# axiom_beta_sensor_cmv12000_tht_v0_16_r1_.net
KiCad netlist of a schematic drawn in EAGLE
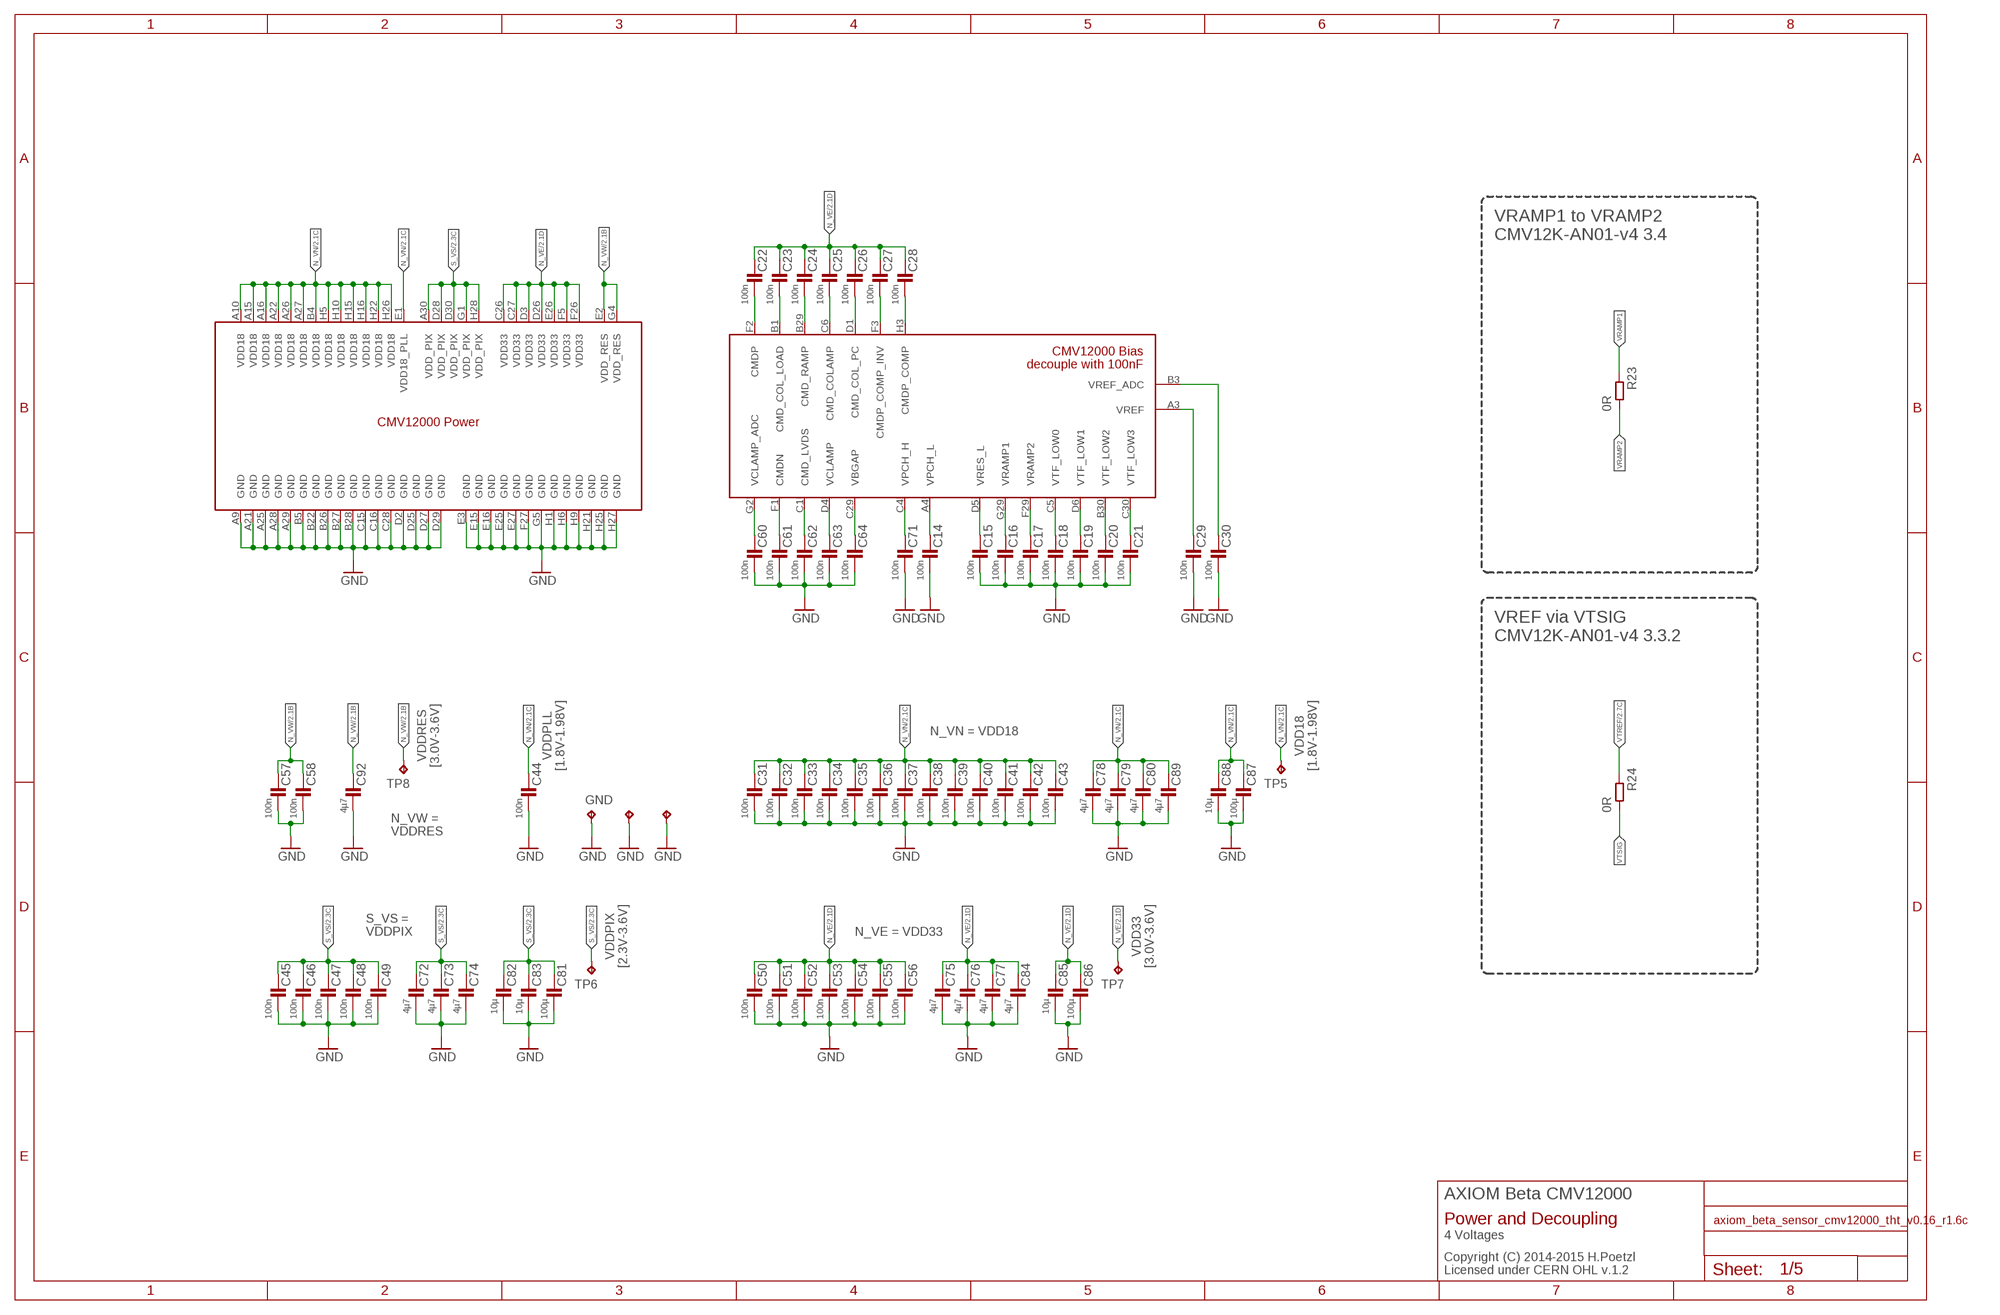
[diagram p0: schematic, sheet 1]
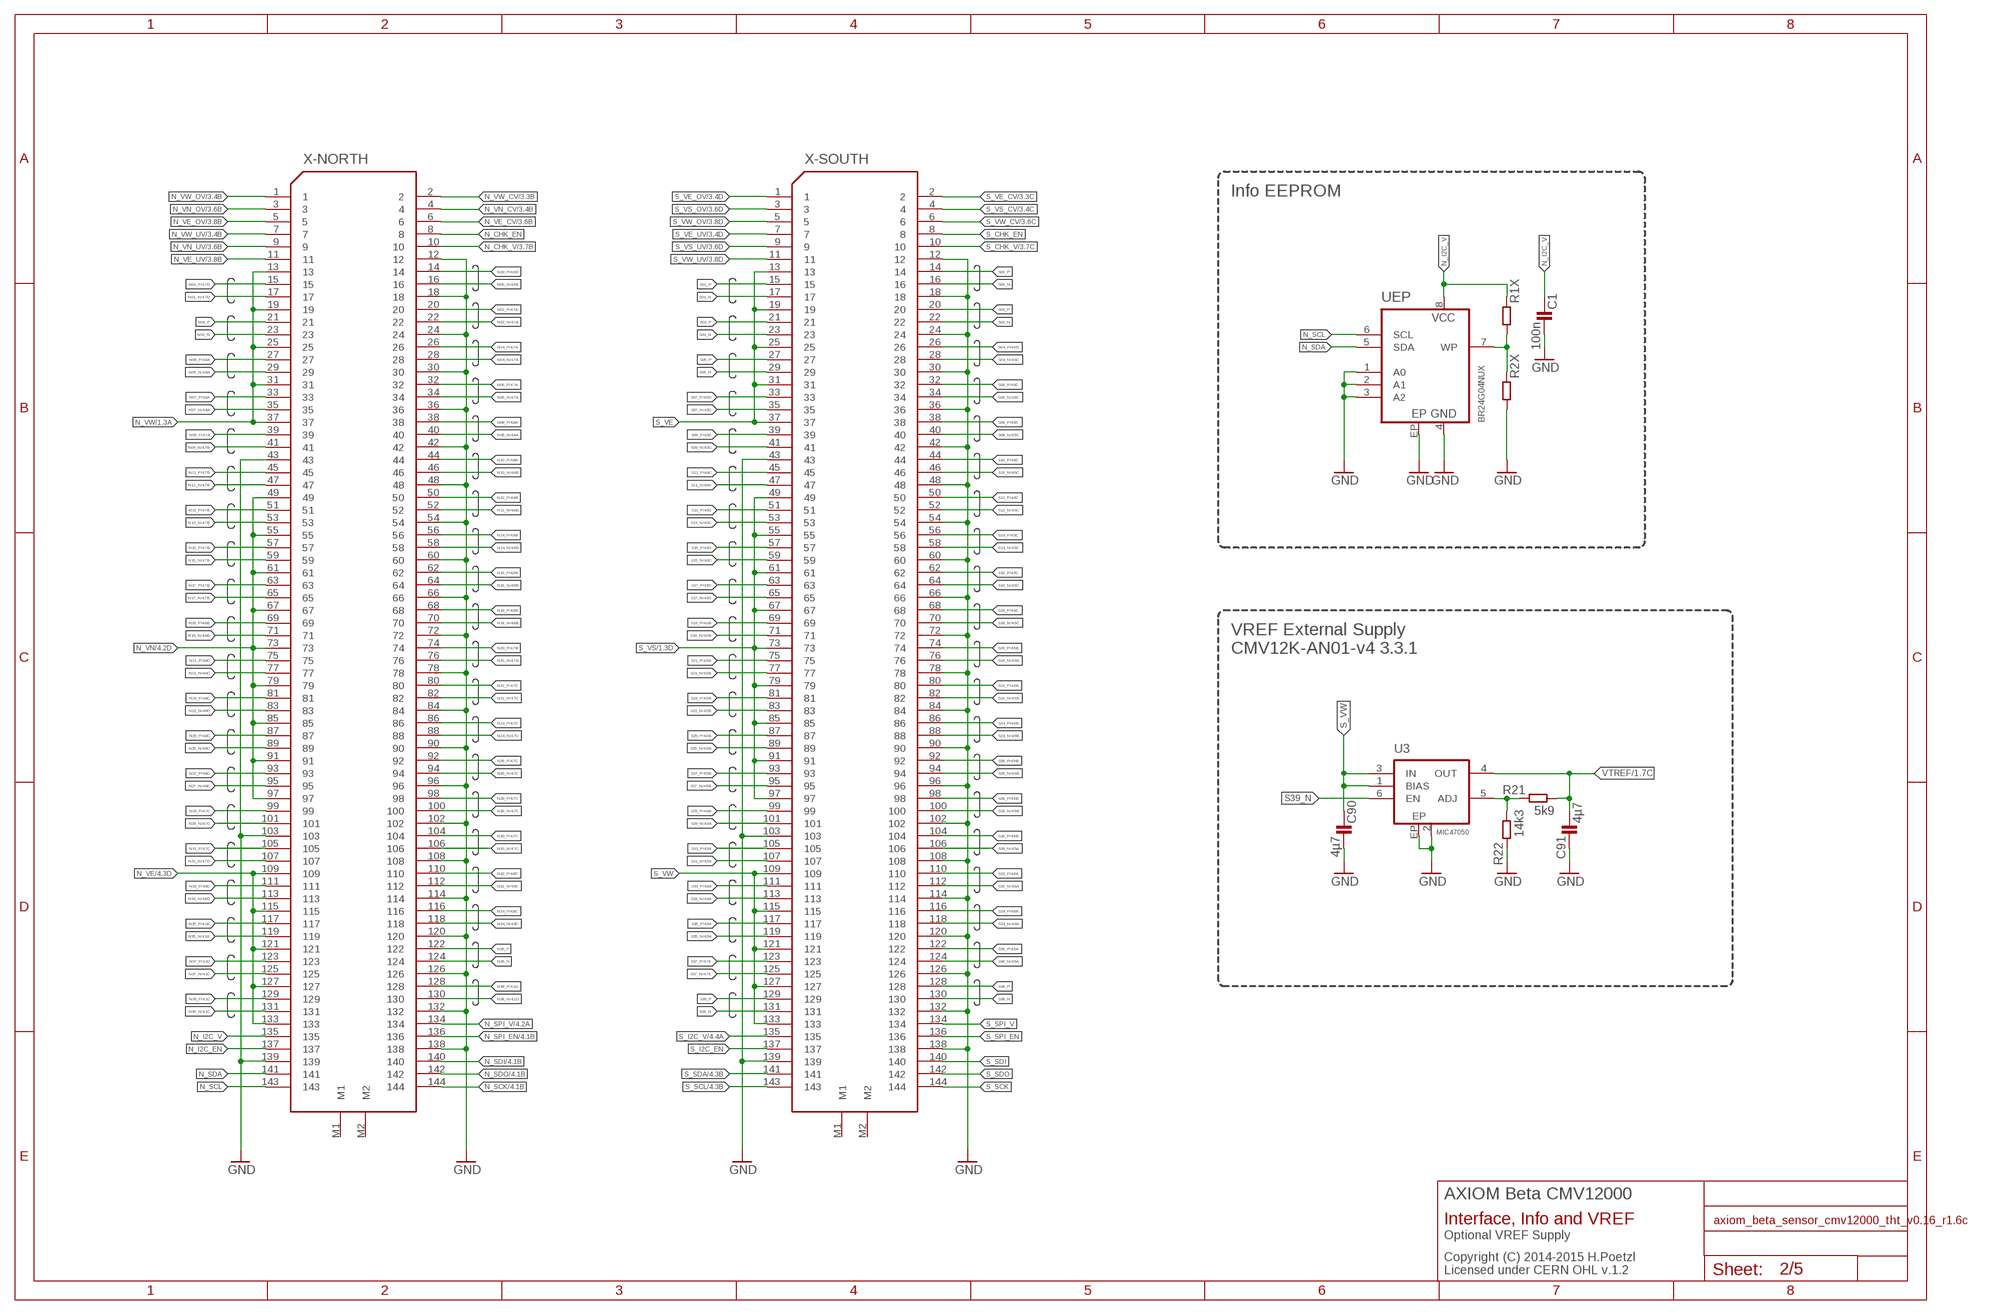
[diagram p1: schematic, sheet 2]
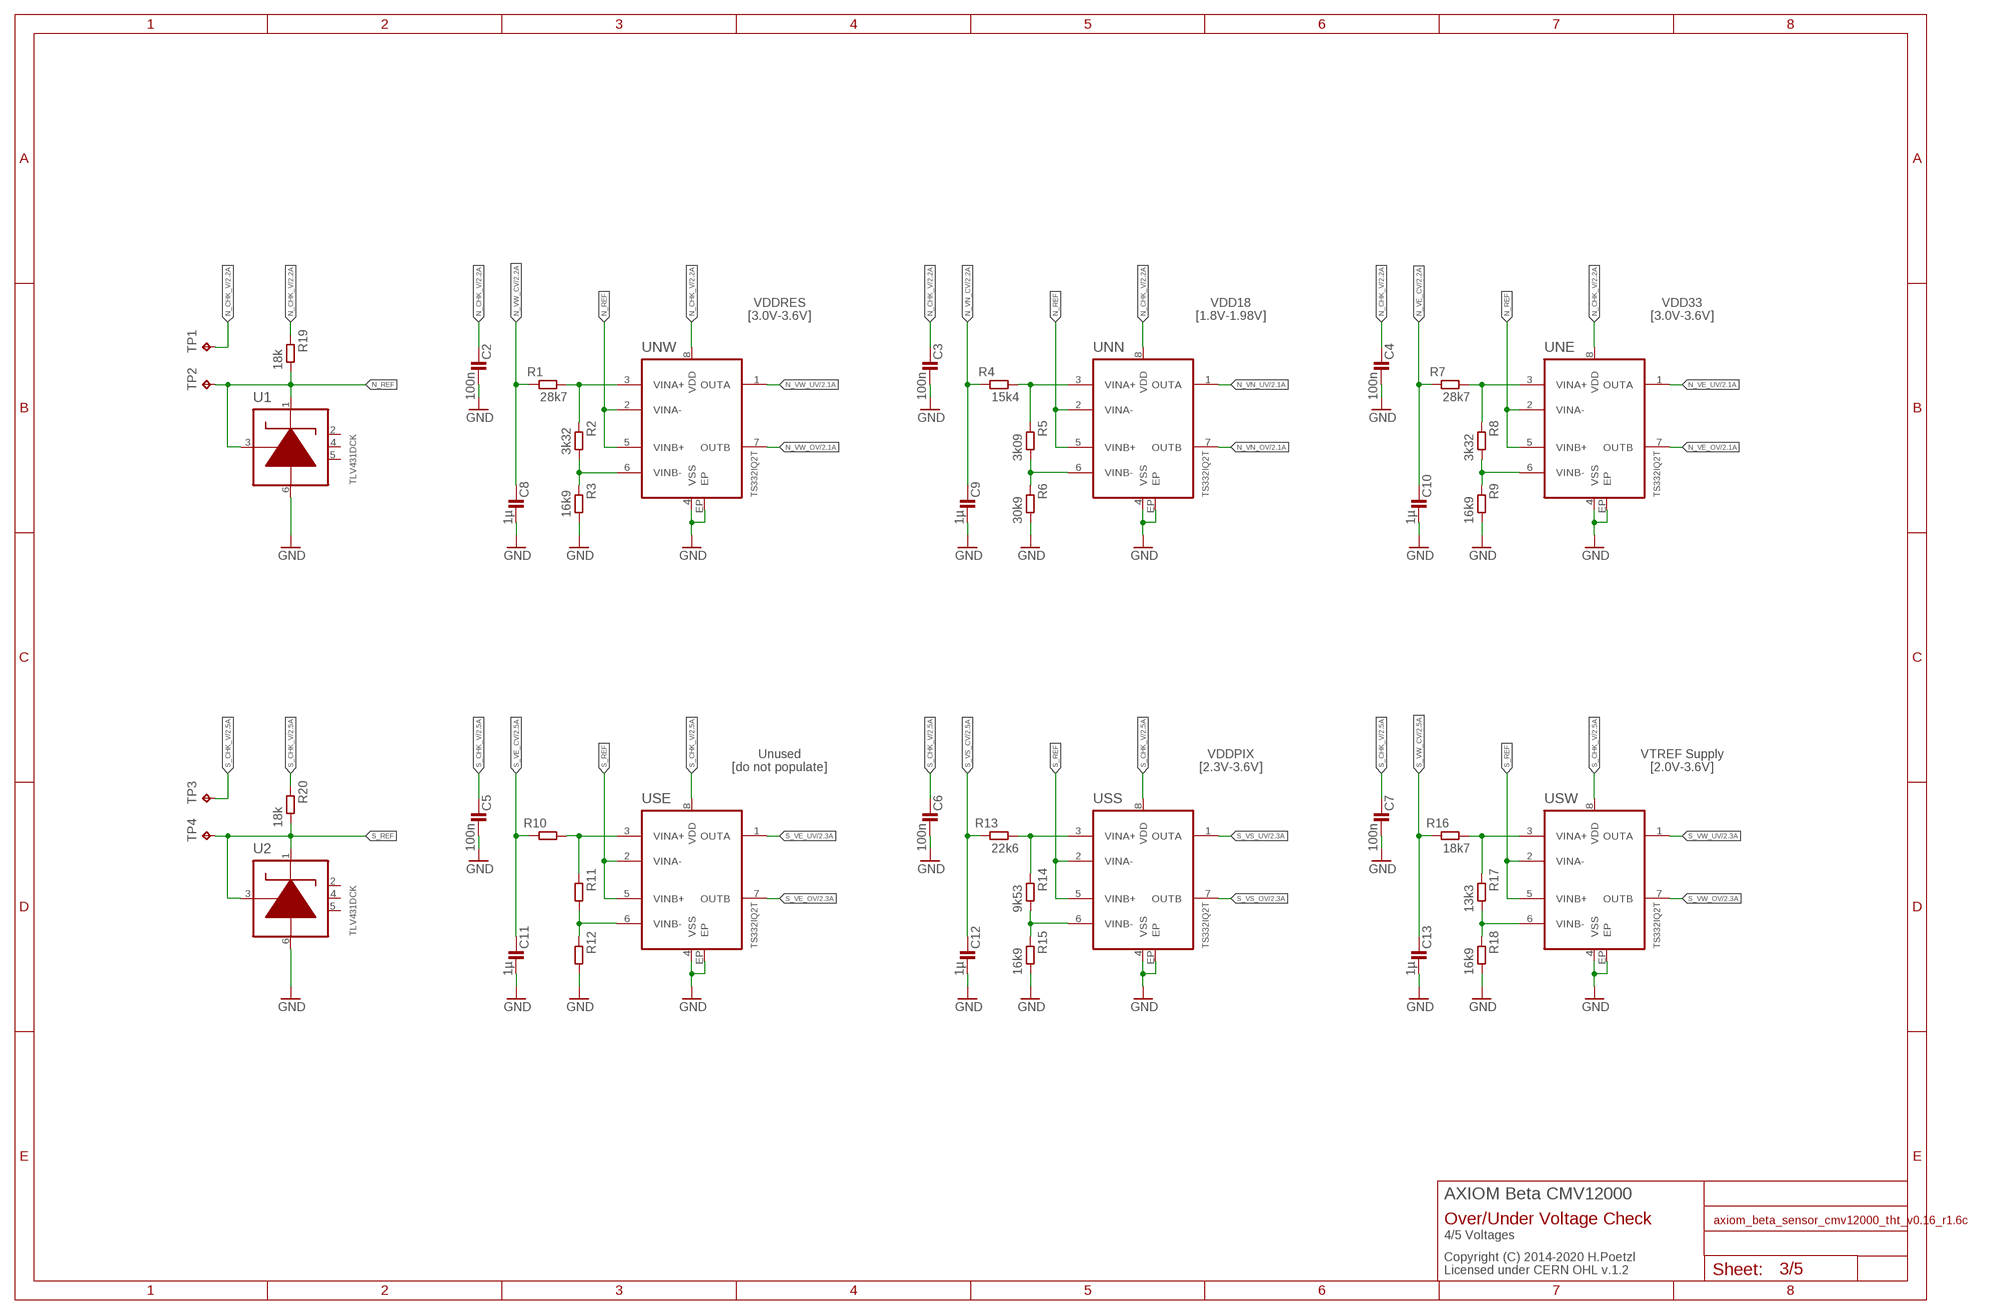
[diagram p2: schematic, sheet 3]
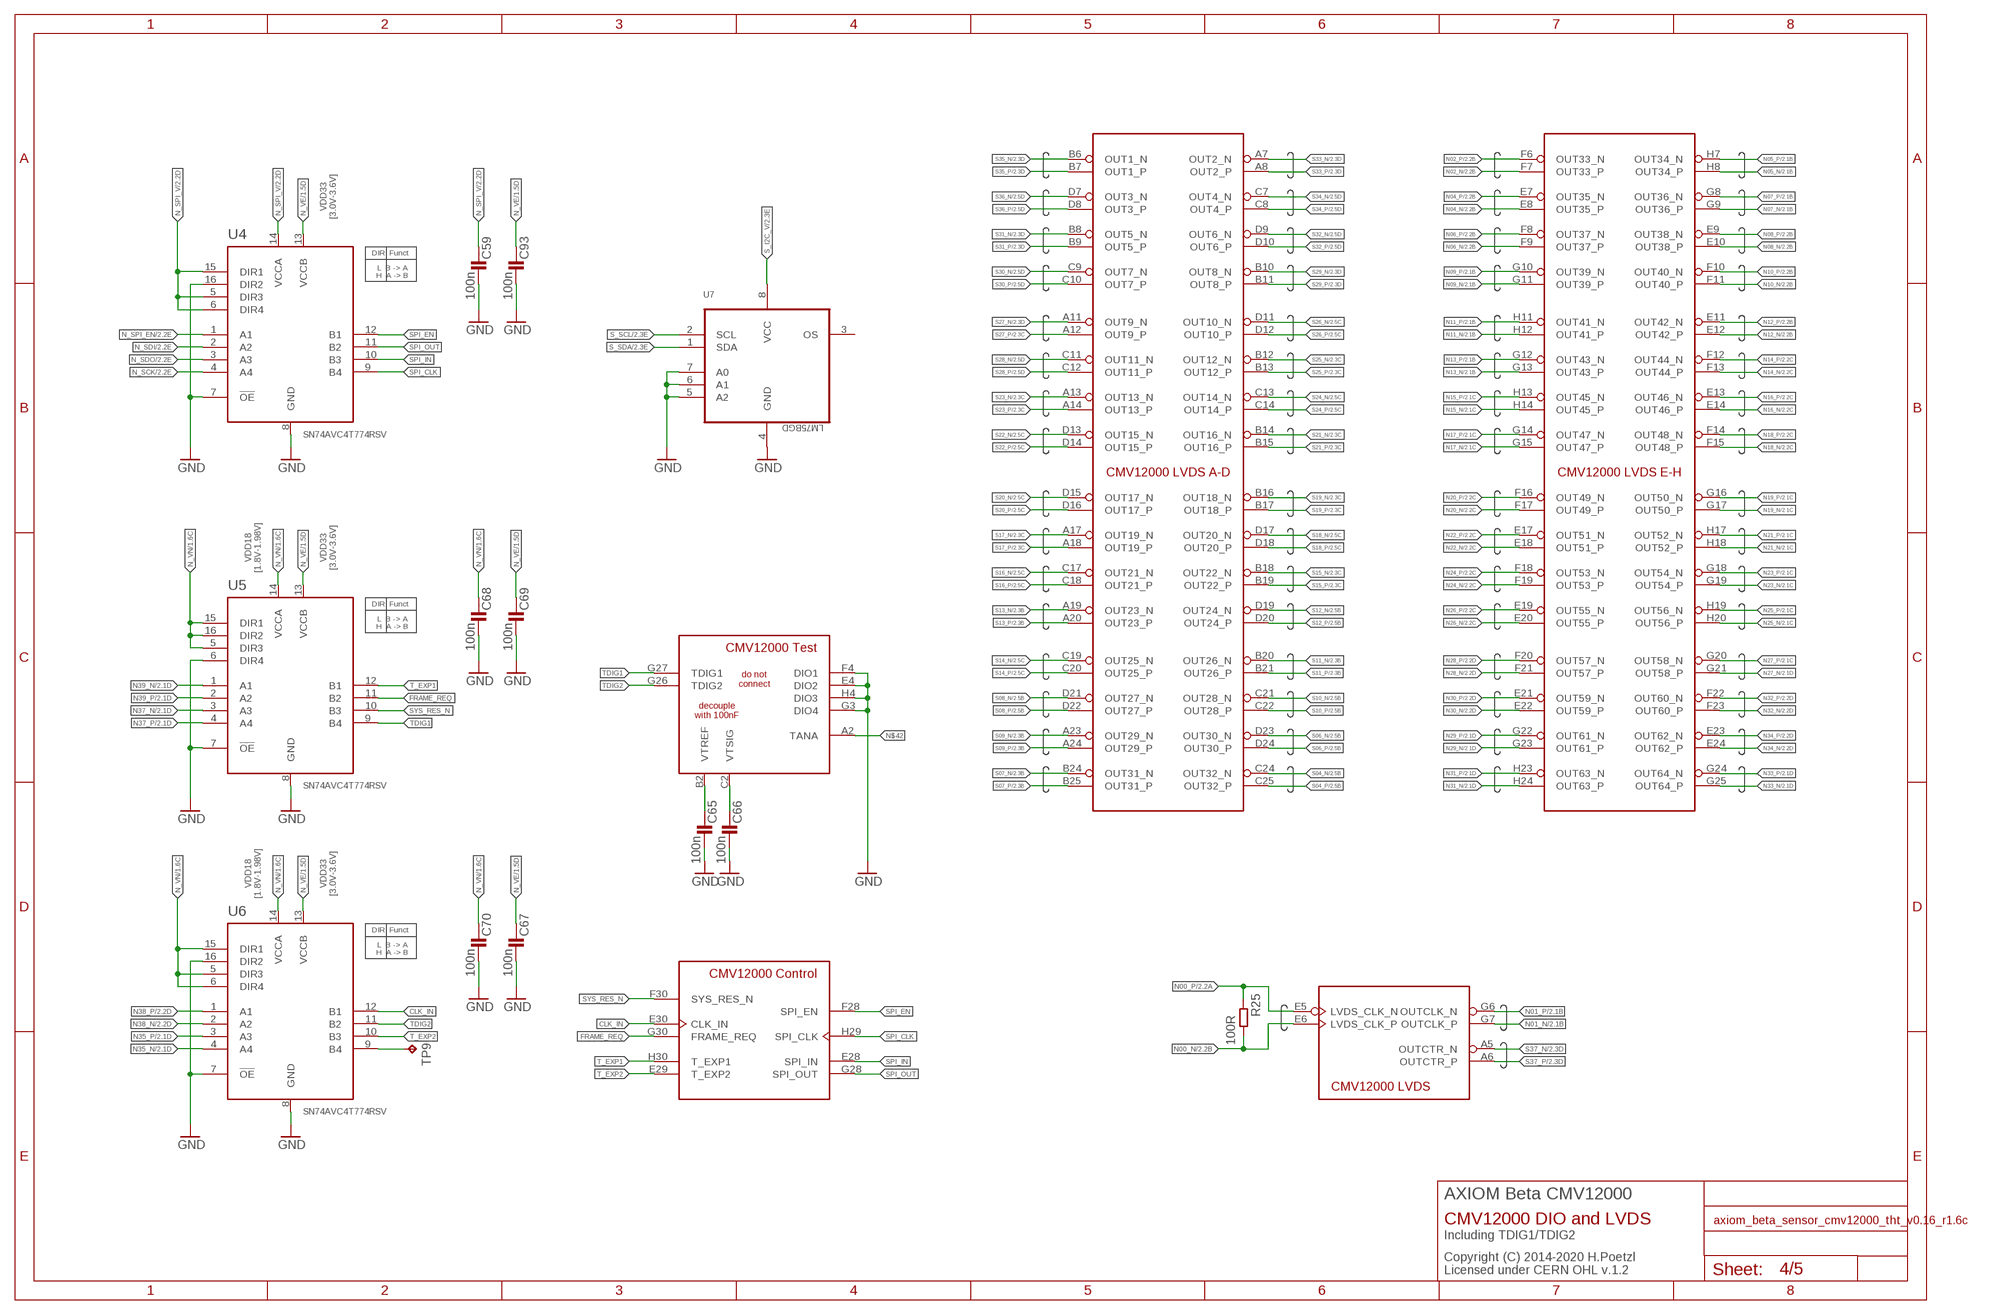
[diagram p3: schematic, sheet 4]
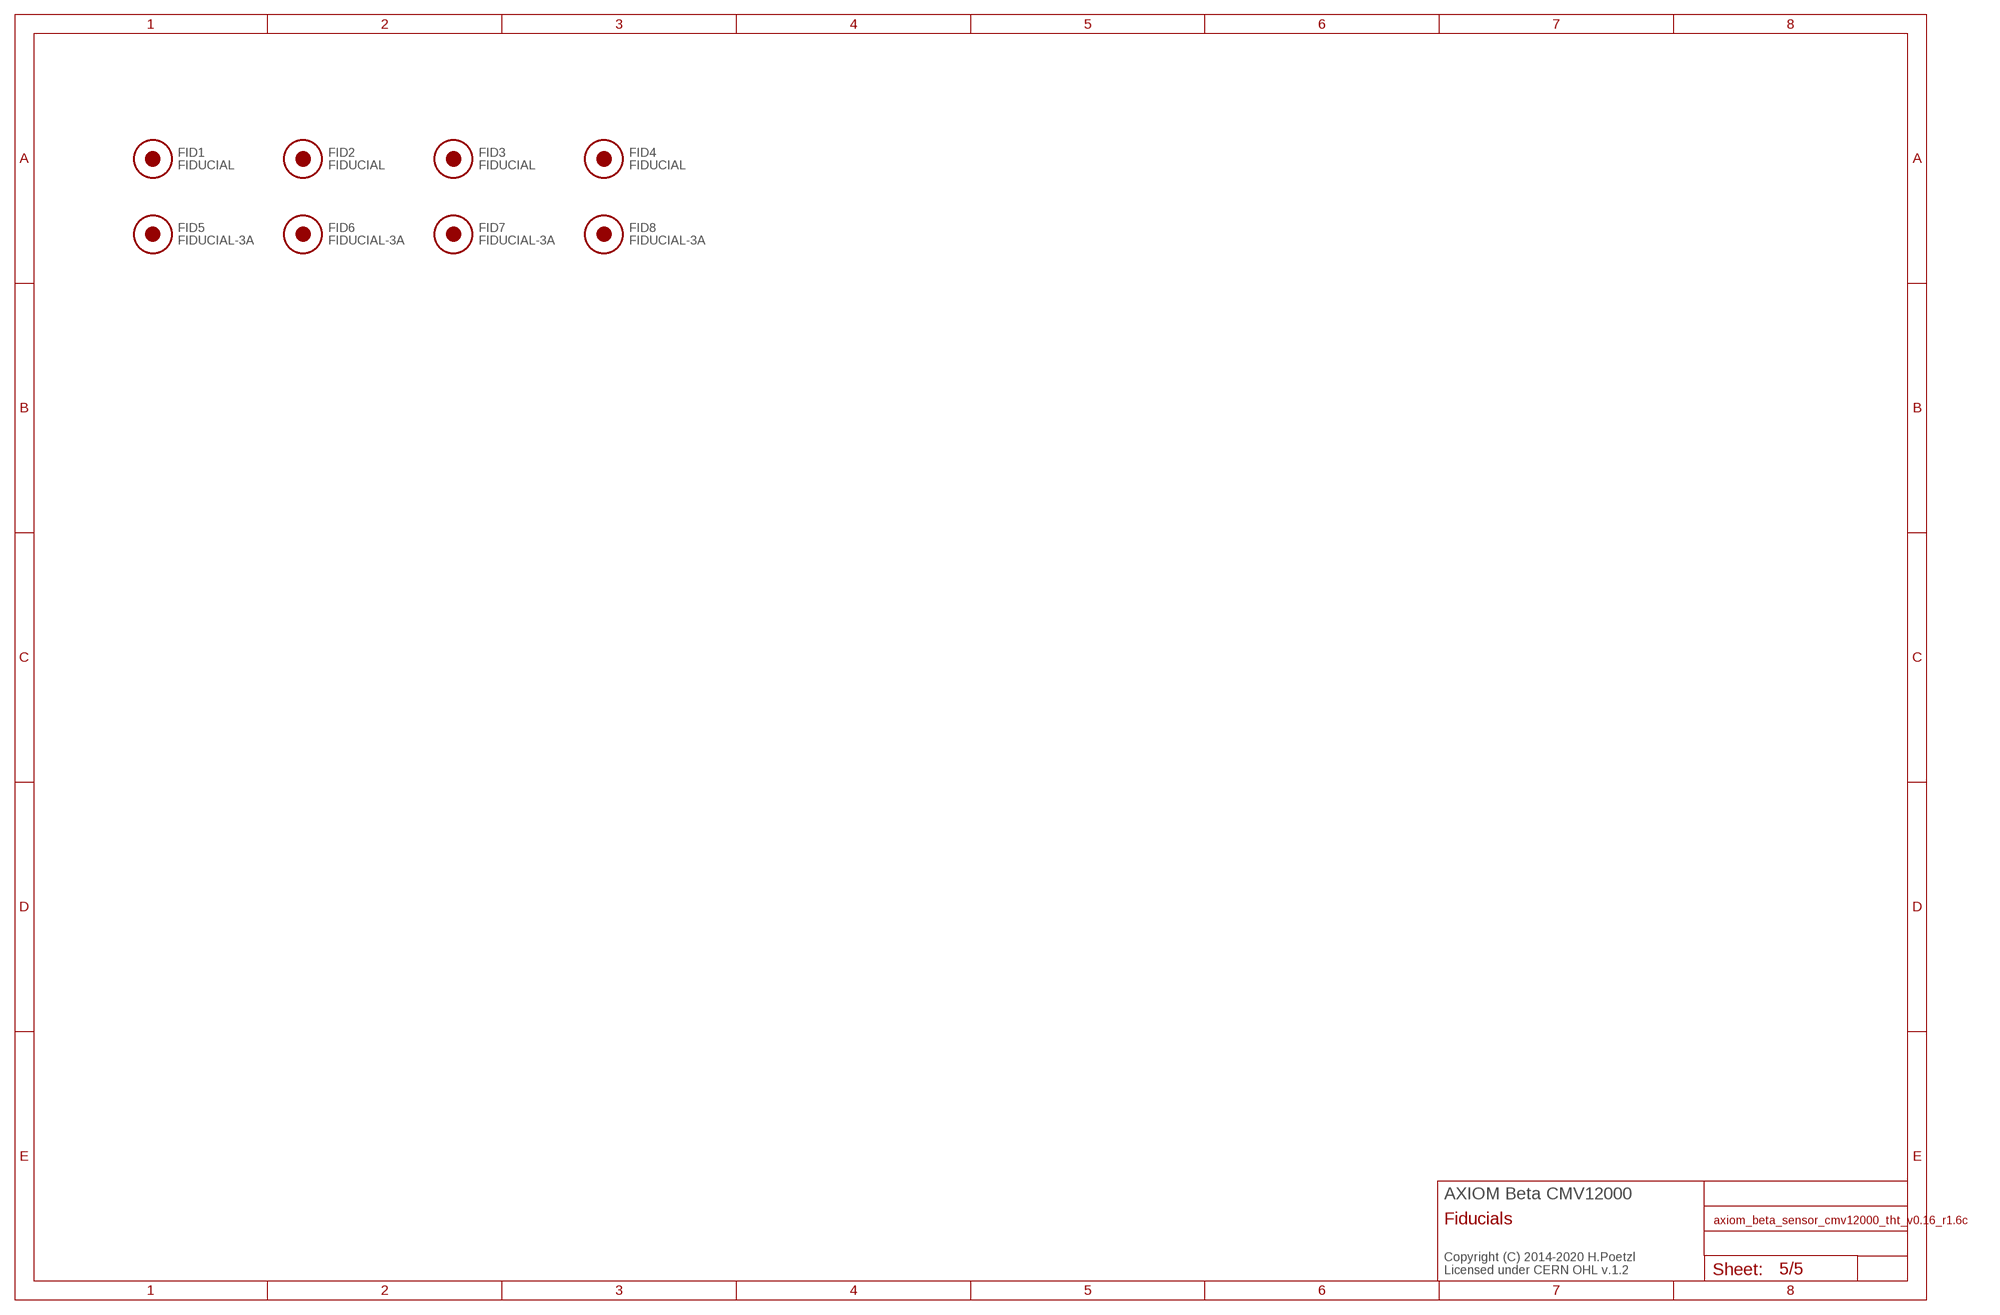
[diagram p4: schematic, sheet 5]

(export (version "E")
  (design (tool "Eeschema 10.0.6"))
  (components
    (comp (ref "C2")
      (value "100n")
      (footprint "eagle-import:0402-C")
      (libsource (lib "eagle-import") (part "C0402-C"))
    )
    (comp (ref "C3")
      (value "100n")
      (footprint "eagle-import:0402-C")
      (libsource (lib "eagle-import") (part "C0402-C"))
    )
    (comp (ref "C4")
      (value "100n")
      (footprint "eagle-import:0402-C")
      (libsource (lib "eagle-import") (part "C0402-C"))
    )
    (comp (ref "C5")
      (value "100n")
      (footprint "eagle-import:0402-C")
      (libsource (lib "eagle-import") (part "C0402-C"))
    )
    (comp (ref "C6")
      (value "100n")
      (footprint "eagle-import:0402-C")
      (libsource (lib "eagle-import") (part "C0402-C"))
    )
    (comp (ref "C7")
      (value "100n")
      (footprint "eagle-import:0402-C")
      (libsource (lib "eagle-import") (part "C0402-C"))
    )
    (comp (ref "C8")
      (value "1µ")
      (footprint "eagle-import:0402-C")
      (libsource (lib "eagle-import") (part "C0402-C"))
    )
    (comp (ref "C9")
      (value "1µ")
      (footprint "eagle-import:0402-C")
      (libsource (lib "eagle-import") (part "C0402-C"))
    )
    (comp (ref "C10")
      (value "1µ")
      (footprint "eagle-import:0402-C")
      (libsource (lib "eagle-import") (part "C0402-C"))
    )
    (comp (ref "C11")
      (value "1µ")
      (footprint "eagle-import:0402-C")
      (libsource (lib "eagle-import") (part "C0402-C"))
    )
    (comp (ref "C12")
      (value "1µ")
      (footprint "eagle-import:0402-C")
      (libsource (lib "eagle-import") (part "C0402-C"))
    )
    (comp (ref "C13")
      (value "1µ")
      (footprint "eagle-import:0402-C")
      (libsource (lib "eagle-import") (part "C0402-C"))
    )
    (comp (ref "R1")
      (value "28k7")
      (footprint "eagle-import:0402-C")
      (libsource (lib "eagle-import") (part "R0402-C"))
    )
    (comp (ref "R2")
      (value "3k32")
      (footprint "eagle-import:0402-C")
      (libsource (lib "eagle-import") (part "R0402-C"))
    )
    (comp (ref "R3")
      (value "16k9")
      (footprint "eagle-import:0402-C")
      (libsource (lib "eagle-import") (part "R0402-C"))
    )
    (comp (ref "R4")
      (value "15k4")
      (footprint "eagle-import:0402-C")
      (libsource (lib "eagle-import") (part "R0402-C"))
    )
    (comp (ref "R5")
      (value "3k09")
      (footprint "eagle-import:0402-C")
      (libsource (lib "eagle-import") (part "R0402-C"))
    )
    (comp (ref "R6")
      (value "30k9")
      (footprint "eagle-import:0402-C")
      (libsource (lib "eagle-import") (part "R0402-C"))
    )
    (comp (ref "R7")
      (value "28k7")
      (footprint "eagle-import:0402-C")
      (libsource (lib "eagle-import") (part "R0402-C"))
    )
    (comp (ref "R8")
      (value "3k32")
      (footprint "eagle-import:0402-C")
      (libsource (lib "eagle-import") (part "R0402-C"))
    )
    (comp (ref "R9")
      (value "16k9")
      (footprint "eagle-import:0402-C")
      (libsource (lib "eagle-import") (part "R0402-C"))
    )
    (comp (ref "R10")
      (value "R0402-C")
      (footprint "eagle-import:0402-C")
      (libsource (lib "eagle-import") (part "R0402-C"))
    )
    (comp (ref "R11")
      (value "R0402-C")
      (footprint "eagle-import:0402-C")
      (libsource (lib "eagle-import") (part "R0402-C"))
    )
    (comp (ref "R12")
      (value "R0402-C")
      (footprint "eagle-import:0402-C")
      (libsource (lib "eagle-import") (part "R0402-C"))
    )
    (comp (ref "R13")
      (value "22k6")
      (footprint "eagle-import:0402-C")
      (libsource (lib "eagle-import") (part "R0402-C"))
    )
    (comp (ref "R14")
      (value "9k53")
      (footprint "eagle-import:0402-C")
      (libsource (lib "eagle-import") (part "R0402-C"))
    )
    (comp (ref "R15")
      (value "16k9")
      (footprint "eagle-import:0402-C")
      (libsource (lib "eagle-import") (part "R0402-C"))
    )
    (comp (ref "R16")
      (value "18k7")
      (footprint "eagle-import:0402-C")
      (libsource (lib "eagle-import") (part "R0402-C"))
    )
    (comp (ref "R17")
      (value "13k3")
      (footprint "eagle-import:0402-C")
      (libsource (lib "eagle-import") (part "R0402-C"))
    )
    (comp (ref "R18")
      (value "16k9")
      (footprint "eagle-import:0402-C")
      (libsource (lib "eagle-import") (part "R0402-C"))
    )
    (comp (ref "R19")
      (value "18k")
      (footprint "eagle-import:0402-C")
      (libsource (lib "eagle-import") (part "R0402-C"))
    )
    (comp (ref "R20")
      (value "18k")
      (footprint "eagle-import:0402-C")
      (libsource (lib "eagle-import") (part "R0402-C"))
    )
    (comp (ref "TP1")
      (value "TPTP10R")
      (footprint "eagle-import:TP10R")
      (libsource (lib "eagle-import") (part "TPTP10R"))
    )
    (comp (ref "TP2")
      (value "TPTP10R")
      (footprint "eagle-import:TP10R")
      (libsource (lib "eagle-import") (part "TPTP10R"))
    )
    (comp (ref "TP3")
      (value "TPTP10R")
      (footprint "eagle-import:TP10R")
      (libsource (lib "eagle-import") (part "TPTP10R"))
    )
    (comp (ref "TP4")
      (value "TPTP10R")
      (footprint "eagle-import:TP10R")
      (libsource (lib "eagle-import") (part "TPTP10R"))
    )
    (comp (ref "U1")
      (value "TLV431DCK")
      (footprint "eagle-import:SOT65P210X110-6N")
      (libsource (lib "eagle-import") (part "TLV431DCK"))
    )
    (comp (ref "U2")
      (value "TLV431DCK")
      (footprint "eagle-import:SOT65P210X110-6N")
      (libsource (lib "eagle-import") (part "TLV431DCK"))
    )
    (comp (ref "UNE")
      (value "TS332IQ2T")
      (footprint "eagle-import:DFN200X200X100-9N")
      (libsource (lib "eagle-import") (part "TS332IQ2T"))
    )
    (comp (ref "UNN")
      (value "TS332IQ2T")
      (footprint "eagle-import:DFN200X200X100-9N")
      (libsource (lib "eagle-import") (part "TS332IQ2T"))
    )
    (comp (ref "UNW")
      (value "TS332IQ2T")
      (footprint "eagle-import:DFN200X200X100-9N")
      (libsource (lib "eagle-import") (part "TS332IQ2T"))
    )
    (comp (ref "USE")
      (value "TS332IQ2T")
      (footprint "eagle-import:DFN200X200X100-9N")
      (libsource (lib "eagle-import") (part "TS332IQ2T"))
    )
    (comp (ref "USS")
      (value "TS332IQ2T")
      (footprint "eagle-import:DFN200X200X100-9N")
      (libsource (lib "eagle-import") (part "TS332IQ2T"))
    )
    (comp (ref "USW")
      (value "TS332IQ2T")
      (footprint "eagle-import:DFN200X200X100-9N")
      (libsource (lib "eagle-import") (part "TS332IQ2T"))
    )
    (comp (ref "FID1")
      (value "FIDUCIAL")
      (footprint "eagle-import:FID_ARROW")
      (libsource (lib "eagle-import") (part "FIDUCIAL"))
    )
    (comp (ref "FID2")
      (value "FIDUCIAL")
      (footprint "eagle-import:FID_ARROW")
      (libsource (lib "eagle-import") (part "FIDUCIAL"))
    )
    (comp (ref "FID3")
      (value "FIDUCIAL")
      (footprint "eagle-import:FID_ARROW")
      (libsource (lib "eagle-import") (part "FIDUCIAL"))
    )
    (comp (ref "FID4")
      (value "FIDUCIAL")
      (footprint "eagle-import:FID_ARROW")
      (libsource (lib "eagle-import") (part "FIDUCIAL"))
    )
    (comp (ref "FID5")
      (value "FIDUCIAL-3A")
      (footprint "eagle-import:FID_3ARROW")
      (libsource (lib "eagle-import") (part "FIDUCIAL-3A"))
    )
    (comp (ref "FID6")
      (value "FIDUCIAL-3A")
      (footprint "eagle-import:FID_3ARROW")
      (libsource (lib "eagle-import") (part "FIDUCIAL-3A"))
    )
    (comp (ref "FID7")
      (value "FIDUCIAL-3A")
      (footprint "eagle-import:FID_3ARROW")
      (libsource (lib "eagle-import") (part "FIDUCIAL-3A"))
    )
    (comp (ref "FID8")
      (value "FIDUCIAL-3A")
      (footprint "eagle-import:FID_3ARROW")
      (libsource (lib "eagle-import") (part "FIDUCIAL-3A"))
    )
    (comp (ref "C59")
      (value "100n")
      (footprint "eagle-import:0402-C")
      (libsource (lib "eagle-import") (part "C0402-C"))
    )
    (comp (ref "C65")
      (value "100n")
      (footprint "eagle-import:0402-C")
      (libsource (lib "eagle-import") (part "C0402-C"))
    )
    (comp (ref "C66")
      (value "100n")
      (footprint "eagle-import:0402-C")
      (libsource (lib "eagle-import") (part "C0402-C"))
    )
    (comp (ref "C67")
      (value "100n")
      (footprint "eagle-import:0402-C")
      (libsource (lib "eagle-import") (part "C0402-C"))
    )
    (comp (ref "C68")
      (value "100n")
      (footprint "eagle-import:0402-C")
      (libsource (lib "eagle-import") (part "C0402-C"))
    )
    (comp (ref "C69")
      (value "100n")
      (footprint "eagle-import:0402-C")
      (libsource (lib "eagle-import") (part "C0402-C"))
    )
    (comp (ref "C70")
      (value "100n")
      (footprint "eagle-import:0402-C")
      (libsource (lib "eagle-import") (part "C0402-C"))
    )
    (comp (ref "C93")
      (value "100n")
      (footprint "eagle-import:0402-C")
      (libsource (lib "eagle-import") (part "C0402-C"))
    )
    (comp (ref "R25")
      (value "100R")
      (footprint "eagle-import:0402-C")
      (libsource (lib "eagle-import") (part "R0402-C"))
    )
    (comp (ref "SENSOR")
      (value "CMV12000ANDON")
      (footprint "eagle-import:10-30-07-237-400T4")
      (libsource (lib "eagle-import") (part "CMV12000ANDON"))
    )
    (comp (ref "TP9")
      (value "TPTP10R")
      (footprint "eagle-import:TP10R")
      (libsource (lib "eagle-import") (part "TPTP10R"))
    )
    (comp (ref "U4")
      (value "SN74AVC4T774RSV")
      (footprint "eagle-import:QFN40P185X265X55-16N")
      (libsource (lib "eagle-import") (part "SN74AVC4T774RSV"))
    )
    (comp (ref "U5")
      (value "SN74AVC4T774RSV")
      (footprint "eagle-import:QFN40P185X265X55-16N")
      (libsource (lib "eagle-import") (part "SN74AVC4T774RSV"))
    )
    (comp (ref "U6")
      (value "SN74AVC4T774RSV")
      (footprint "eagle-import:QFN40P185X265X55-16N")
      (libsource (lib "eagle-import") (part "SN74AVC4T774RSV"))
    )
    (comp (ref "U7")
      (value "LM75BGD")
      (footprint "eagle-import:SOT996-2_3")
      (libsource (lib "eagle-import") (part "LM75BGD"))
    )
    (comp (ref "C14")
      (value "100n")
      (footprint "eagle-import:0402-C")
      (libsource (lib "eagle-import") (part "C0402-C"))
    )
    (comp (ref "C15")
      (value "100n")
      (footprint "eagle-import:0402-C")
      (libsource (lib "eagle-import") (part "C0402-C"))
    )
    (comp (ref "C16")
      (value "100n")
      (footprint "eagle-import:0402-C")
      (libsource (lib "eagle-import") (part "C0402-C"))
    )
    (comp (ref "C17")
      (value "100n")
      (footprint "eagle-import:0402-C")
      (libsource (lib "eagle-import") (part "C0402-C"))
    )
    (comp (ref "C18")
      (value "100n")
      (footprint "eagle-import:0402-C")
      (libsource (lib "eagle-import") (part "C0402-C"))
    )
    (comp (ref "C19")
      (value "100n")
      (footprint "eagle-import:0402-C")
      (libsource (lib "eagle-import") (part "C0402-C"))
    )
    (comp (ref "C20")
      (value "100n")
      (footprint "eagle-import:0402-C")
      (libsource (lib "eagle-import") (part "C0402-C"))
    )
    (comp (ref "C21")
      (value "100n")
      (footprint "eagle-import:0402-C")
      (libsource (lib "eagle-import") (part "C0402-C"))
    )
    (comp (ref "C22")
      (value "100n")
      (footprint "eagle-import:0402-C")
      (libsource (lib "eagle-import") (part "C0402-C"))
    )
    (comp (ref "C23")
      (value "100n")
      (footprint "eagle-import:0402-C")
      (libsource (lib "eagle-import") (part "C0402-C"))
    )
    (comp (ref "C24")
      (value "100n")
      (footprint "eagle-import:0402-C")
      (libsource (lib "eagle-import") (part "C0402-C"))
    )
    (comp (ref "C25")
      (value "100n")
      (footprint "eagle-import:0402-C")
      (libsource (lib "eagle-import") (part "C0402-C"))
    )
    (comp (ref "C26")
      (value "100n")
      (footprint "eagle-import:0402-C")
      (libsource (lib "eagle-import") (part "C0402-C"))
    )
    (comp (ref "C27")
      (value "100n")
      (footprint "eagle-import:0402-C")
      (libsource (lib "eagle-import") (part "C0402-C"))
    )
    (comp (ref "C28")
      (value "100n")
      (footprint "eagle-import:0402-C")
      (libsource (lib "eagle-import") (part "C0402-C"))
    )
    (comp (ref "C29")
      (value "100n")
      (footprint "eagle-import:0402-C")
      (libsource (lib "eagle-import") (part "C0402-C"))
    )
    (comp (ref "C30")
      (value "100n")
      (footprint "eagle-import:0402-C")
      (libsource (lib "eagle-import") (part "C0402-C"))
    )
    (comp (ref "C31")
      (value "100n")
      (footprint "eagle-import:0402-C")
      (libsource (lib "eagle-import") (part "C0402-C"))
    )
    (comp (ref "C32")
      (value "100n")
      (footprint "eagle-import:0402-C")
      (libsource (lib "eagle-import") (part "C0402-C"))
    )
    (comp (ref "C33")
      (value "100n")
      (footprint "eagle-import:0402-C")
      (libsource (lib "eagle-import") (part "C0402-C"))
    )
    (comp (ref "C34")
      (value "100n")
      (footprint "eagle-import:0402-C")
      (libsource (lib "eagle-import") (part "C0402-C"))
    )
    (comp (ref "C35")
      (value "100n")
      (footprint "eagle-import:0402-C")
      (libsource (lib "eagle-import") (part "C0402-C"))
    )
    (comp (ref "C36")
      (value "100n")
      (footprint "eagle-import:0402-C")
      (libsource (lib "eagle-import") (part "C0402-C"))
    )
    (comp (ref "C37")
      (value "100n")
      (footprint "eagle-import:0402-C")
      (libsource (lib "eagle-import") (part "C0402-C"))
    )
    (comp (ref "C38")
      (value "100n")
      (footprint "eagle-import:0402-C")
      (libsource (lib "eagle-import") (part "C0402-C"))
    )
    (comp (ref "C39")
      (value "100n")
      (footprint "eagle-import:0402-C")
      (libsource (lib "eagle-import") (part "C0402-C"))
    )
    (comp (ref "C40")
      (value "100n")
      (footprint "eagle-import:0402-C")
      (libsource (lib "eagle-import") (part "C0402-C"))
    )
    (comp (ref "C41")
      (value "100n")
      (footprint "eagle-import:0402-C")
      (libsource (lib "eagle-import") (part "C0402-C"))
    )
    (comp (ref "C42")
      (value "100n")
      (footprint "eagle-import:0402-C")
      (libsource (lib "eagle-import") (part "C0402-C"))
    )
    (comp (ref "C43")
      (value "100n")
      (footprint "eagle-import:0402-C")
      (libsource (lib "eagle-import") (part "C0402-C"))
    )
    (comp (ref "C44")
      (value "100n")
      (footprint "eagle-import:0402-C")
      (libsource (lib "eagle-import") (part "C0402-C"))
    )
    (comp (ref "C45")
      (value "100n")
      (footprint "eagle-import:0402-C")
      (libsource (lib "eagle-import") (part "C0402-C"))
    )
    (comp (ref "C46")
      (value "100n")
      (footprint "eagle-import:0402-C")
      (libsource (lib "eagle-import") (part "C0402-C"))
    )
    (comp (ref "C47")
      (value "100n")
      (footprint "eagle-import:0402-C")
      (libsource (lib "eagle-import") (part "C0402-C"))
    )
    (comp (ref "C48")
      (value "100n")
      (footprint "eagle-import:0402-C")
      (libsource (lib "eagle-import") (part "C0402-C"))
    )
    (comp (ref "C49")
      (value "100n")
      (footprint "eagle-import:0402-C")
      (libsource (lib "eagle-import") (part "C0402-C"))
    )
    (comp (ref "C50")
      (value "100n")
      (footprint "eagle-import:0402-C")
      (libsource (lib "eagle-import") (part "C0402-C"))
    )
    (comp (ref "C51")
      (value "100n")
      (footprint "eagle-import:0402-C")
      (libsource (lib "eagle-import") (part "C0402-C"))
    )
    (comp (ref "C52")
      (value "100n")
      (footprint "eagle-import:0402-C")
      (libsource (lib "eagle-import") (part "C0402-C"))
    )
    (comp (ref "C53")
      (value "100n")
      (footprint "eagle-import:0402-C")
      (libsource (lib "eagle-import") (part "C0402-C"))
    )
    (comp (ref "C54")
      (value "100n")
      (footprint "eagle-import:0402-C")
      (libsource (lib "eagle-import") (part "C0402-C"))
    )
    (comp (ref "C55")
      (value "100n")
      (footprint "eagle-import:0402-C")
      (libsource (lib "eagle-import") (part "C0402-C"))
    )
    (comp (ref "C56")
      (value "100n")
      (footprint "eagle-import:0402-C")
      (libsource (lib "eagle-import") (part "C0402-C"))
    )
    (comp (ref "C57")
      (value "100n")
      (footprint "eagle-import:0402-C")
      (libsource (lib "eagle-import") (part "C0402-C"))
    )
    (comp (ref "C58")
      (value "100n")
      (footprint "eagle-import:0402-C")
      (libsource (lib "eagle-import") (part "C0402-C"))
    )
    (comp (ref "C60")
      (value "100n")
      (footprint "eagle-import:0402-C")
      (libsource (lib "eagle-import") (part "C0402-C"))
    )
    (comp (ref "C61")
      (value "100n")
      (footprint "eagle-import:0402-C")
      (libsource (lib "eagle-import") (part "C0402-C"))
    )
    (comp (ref "C62")
      (value "100n")
      (footprint "eagle-import:0402-C")
      (libsource (lib "eagle-import") (part "C0402-C"))
    )
    (comp (ref "C63")
      (value "100n")
      (footprint "eagle-import:0402-C")
      (libsource (lib "eagle-import") (part "C0402-C"))
    )
    (comp (ref "C64")
      (value "100n")
      (footprint "eagle-import:0402-C")
      (libsource (lib "eagle-import") (part "C0402-C"))
    )
    (comp (ref "C71")
      (value "100n")
      (footprint "eagle-import:0402-C")
      (libsource (lib "eagle-import") (part "C0402-C"))
    )
    (comp (ref "C72")
      (value "4µ7")
      (footprint "eagle-import:0402-B")
      (libsource (lib "eagle-import") (part "C0402-B"))
    )
    (comp (ref "C73")
      (value "4µ7")
      (footprint "eagle-import:0402-C")
      (libsource (lib "eagle-import") (part "C0402-C"))
    )
    (comp (ref "C74")
      (value "4µ7")
      (footprint "eagle-import:0402-C")
      (libsource (lib "eagle-import") (part "C0402-C"))
    )
    (comp (ref "C75")
      (value "4µ7")
      (footprint "eagle-import:0402-C")
      (libsource (lib "eagle-import") (part "C0402-C"))
    )
    (comp (ref "C76")
      (value "4µ7")
      (footprint "eagle-import:0402-C")
      (libsource (lib "eagle-import") (part "C0402-C"))
    )
    (comp (ref "C77")
      (value "4µ7")
      (footprint "eagle-import:0402-B")
      (libsource (lib "eagle-import") (part "C0402-B"))
    )
    (comp (ref "C78")
      (value "4µ7")
      (footprint "eagle-import:0402-B")
      (libsource (lib "eagle-import") (part "C0402-B"))
    )
    (comp (ref "C79")
      (value "4µ7")
      (footprint "eagle-import:0402-C")
      (libsource (lib "eagle-import") (part "C0402-C"))
    )
    (comp (ref "C80")
      (value "4µ7")
      (footprint "eagle-import:0402-C")
      (libsource (lib "eagle-import") (part "C0402-C"))
    )
    (comp (ref "C81")
      (value "100µ")
      (footprint "eagle-import:1206-B")
      (libsource (lib "eagle-import") (part "C1206-B"))
    )
    (comp (ref "C82")
      (value "10µ")
      (footprint "eagle-import:0603-C")
      (libsource (lib "eagle-import") (part "C0603-C"))
    )
    (comp (ref "C83")
      (value "10µ")
      (footprint "eagle-import:0603-C")
      (libsource (lib "eagle-import") (part "C0603-C"))
    )
    (comp (ref "C84")
      (value "4µ7")
      (footprint "eagle-import:0402-C")
      (libsource (lib "eagle-import") (part "C0402-C"))
    )
    (comp (ref "C85")
      (value "10µ")
      (footprint "eagle-import:0603-C")
      (libsource (lib "eagle-import") (part "C0603-C"))
    )
    (comp (ref "C86")
      (value "100µ")
      (footprint "eagle-import:1206-B")
      (libsource (lib "eagle-import") (part "C1206-B"))
    )
    (comp (ref "C87")
      (value "100µ")
      (footprint "eagle-import:1206-B")
      (libsource (lib "eagle-import") (part "C1206-B"))
    )
    (comp (ref "C88")
      (value "10µ")
      (footprint "eagle-import:0603-C")
      (libsource (lib "eagle-import") (part "C0603-C"))
    )
    (comp (ref "C89")
      (value "4µ7")
      (footprint "eagle-import:0402-C")
      (libsource (lib "eagle-import") (part "C0402-C"))
    )
    (comp (ref "C92")
      (value "4µ7")
      (footprint "eagle-import:0402-C")
      (libsource (lib "eagle-import") (part "C0402-C"))
    )
    (comp (ref "GND")
      (value "TPTP10R")
      (footprint "eagle-import:TP10R")
      (libsource (lib "eagle-import") (part "TPTP10R"))
    )
    (comp (ref "GND75")
      (value "TPTP10R")
      (footprint "eagle-import:TP10R")
      (libsource (lib "eagle-import") (part "TPTP10R"))
    )
    (comp (ref "GND77")
      (value "TPTP10R")
      (footprint "eagle-import:TP10R")
      (libsource (lib "eagle-import") (part "TPTP10R"))
    )
    (comp (ref "R23")
      (value "0R")
      (footprint "eagle-import:0402-C")
      (libsource (lib "eagle-import") (part "R0402-C"))
    )
    (comp (ref "R24")
      (value "0R")
      (footprint "eagle-import:0402-C")
      (libsource (lib "eagle-import") (part "R0402-C"))
    )
    (comp (ref "TP5")
      (value "TPTP10R")
      (footprint "eagle-import:TP10R")
      (libsource (lib "eagle-import") (part "TPTP10R"))
    )
    (comp (ref "TP6")
      (value "TPTP10R")
      (footprint "eagle-import:TP10R")
      (libsource (lib "eagle-import") (part "TPTP10R"))
    )
    (comp (ref "TP7")
      (value "TPTP10R")
      (footprint "eagle-import:TP10R")
      (libsource (lib "eagle-import") (part "TPTP10R"))
    )
    (comp (ref "TP8")
      (value "TPTP10R")
      (footprint "eagle-import:TP10R")
      (libsource (lib "eagle-import") (part "TPTP10R"))
    )
    (comp (ref "C1")
      (value "100n")
      (footprint "eagle-import:0402-C")
      (libsource (lib "eagle-import") (part "C0402-C"))
    )
    (comp (ref "C90")
      (value "4µ7")
      (footprint "eagle-import:0402-C")
      (libsource (lib "eagle-import") (part "C0402-C"))
    )
    (comp (ref "C91")
      (value "4µ7")
      (footprint "eagle-import:0402-C")
      (libsource (lib "eagle-import") (part "C0402-C"))
    )
    (comp (ref "R1X")
      (value "R0402-C")
      (footprint "eagle-import:0402-C")
      (libsource (lib "eagle-import") (part "R0402-C"))
    )
    (comp (ref "R2X")
      (value "R0402-C")
      (footprint "eagle-import:0402-C")
      (libsource (lib "eagle-import") (part "R0402-C"))
    )
    (comp (ref "R21")
      (value "5k9")
      (footprint "eagle-import:0402-C")
      (libsource (lib "eagle-import") (part "R0402-C"))
    )
    (comp (ref "R22")
      (value "14k3")
      (footprint "eagle-import:0402-C")
      (libsource (lib "eagle-import") (part "R0402-C"))
    )
    (comp (ref "U3")
      (value "MIC47050")
      (footprint "eagle-import:MLF-6")
      (libsource (lib "eagle-import") (part "MIC47050-ADJ"))
    )
    (comp (ref "UEP")
      (value "BR24G04NUX")
      (footprint "eagle-import:DFN200X300X100-9N")
      (libsource (lib "eagle-import") (part "BR24G04NUX"))
    )
    (comp (ref "X-NORTH")
      (value "FX10-144P")
      (footprint "eagle-import:FX10A-144P")
      (libsource (lib "eagle-import") (part "FX10-144P"))
    )
    (comp (ref "X-SOUTH")
      (value "FX10-144P")
      (footprint "eagle-import:FX10A-144P")
      (libsource (lib "eagle-import") (part "FX10-144P"))
    )
  )
  (nets
    (net (code "1") (name "CLK_IN") (class "Default")
      (node (ref "SENSOR") (pin "E30") (pinfunction "CLK_IN_E30") (pintype "input"))
      (node (ref "U6") (pin "12") (pinfunction "B1_12") (pintype "bidirectional"))
    )
    (net (code "2") (name "FRAME_REQ") (class "Default")
      (node (ref "SENSOR") (pin "G30") (pinfunction "FRAME_REQ_G30") (pintype "input"))
      (node (ref "U5") (pin "11") (pinfunction "B2_11") (pintype "bidirectional"))
    )
    (net (code "3") (name "GND") (class "Default")
      (node (ref "C1") (pin "2") (pinfunction "2_2") (pintype "passive"))
      (node (ref "C10") (pin "2") (pinfunction "2_2") (pintype "passive"))
      (node (ref "C11") (pin "2") (pinfunction "2_2") (pintype "passive"))
      (node (ref "C12") (pin "2") (pinfunction "2_2") (pintype "passive"))
      (node (ref "C13") (pin "2") (pinfunction "2_2") (pintype "passive"))
      (node (ref "C14") (pin "2") (pinfunction "2_2") (pintype "passive"))
      (node (ref "C15") (pin "2") (pinfunction "2_2") (pintype "passive"))
      (node (ref "C16") (pin "2") (pinfunction "2_2") (pintype "passive"))
      (node (ref "C17") (pin "2") (pinfunction "2_2") (pintype "passive"))
      (node (ref "C18") (pin "2") (pinfunction "2_2") (pintype "passive"))
      (node (ref "C19") (pin "2") (pinfunction "2_2") (pintype "passive"))
      (node (ref "C2") (pin "2") (pinfunction "2_2") (pintype "passive"))
      (node (ref "C20") (pin "2") (pinfunction "2_2") (pintype "passive"))
      (node (ref "C21") (pin "2") (pinfunction "2_2") (pintype "passive"))
      (node (ref "C29") (pin "2") (pinfunction "2_2") (pintype "passive"))
      (node (ref "C3") (pin "2") (pinfunction "2_2") (pintype "passive"))
      (node (ref "C30") (pin "2") (pinfunction "2_2") (pintype "passive"))
      (node (ref "C31") (pin "2") (pinfunction "2_2") (pintype "passive"))
      (node (ref "C32") (pin "2") (pinfunction "2_2") (pintype "passive"))
      (node (ref "C33") (pin "2") (pinfunction "2_2") (pintype "passive"))
      (node (ref "C34") (pin "2") (pinfunction "2_2") (pintype "passive"))
      (node (ref "C35") (pin "2") (pinfunction "2_2") (pintype "passive"))
      (node (ref "C36") (pin "2") (pinfunction "2_2") (pintype "passive"))
      (node (ref "C37") (pin "2") (pinfunction "2_2") (pintype "passive"))
      (node (ref "C38") (pin "2") (pinfunction "2_2") (pintype "passive"))
      (node (ref "C39") (pin "2") (pinfunction "2_2") (pintype "passive"))
      (node (ref "C4") (pin "2") (pinfunction "2_2") (pintype "passive"))
      (node (ref "C40") (pin "2") (pinfunction "2_2") (pintype "passive"))
      (node (ref "C41") (pin "2") (pinfunction "2_2") (pintype "passive"))
      (node (ref "C42") (pin "2") (pinfunction "2_2") (pintype "passive"))
      (node (ref "C43") (pin "2") (pinfunction "2_2") (pintype "passive"))
      (node (ref "C44") (pin "2") (pinfunction "2_2") (pintype "passive"))
      (node (ref "C45") (pin "2") (pinfunction "2_2") (pintype "passive"))
      (node (ref "C46") (pin "2") (pinfunction "2_2") (pintype "passive"))
      (node (ref "C47") (pin "2") (pinfunction "2_2") (pintype "passive"))
      (node (ref "C48") (pin "2") (pinfunction "2_2") (pintype "passive"))
      (node (ref "C49") (pin "2") (pinfunction "2_2") (pintype "passive"))
      (node (ref "C5") (pin "2") (pinfunction "2_2") (pintype "passive"))
      (node (ref "C50") (pin "2") (pinfunction "2_2") (pintype "passive"))
      (node (ref "C51") (pin "2") (pinfunction "2_2") (pintype "passive"))
      (node (ref "C52") (pin "2") (pinfunction "2_2") (pintype "passive"))
      (node (ref "C53") (pin "2") (pinfunction "2_2") (pintype "passive"))
      (node (ref "C54") (pin "2") (pinfunction "2_2") (pintype "passive"))
      (node (ref "C55") (pin "2") (pinfunction "2_2") (pintype "passive"))
      (node (ref "C56") (pin "2") (pinfunction "2_2") (pintype "passive"))
      (node (ref "C57") (pin "2") (pinfunction "2_2") (pintype "passive"))
      (node (ref "C58") (pin "2") (pinfunction "2_2") (pintype "passive"))
      (node (ref "C59") (pin "2") (pinfunction "2_2") (pintype "passive"))
      (node (ref "C6") (pin "2") (pinfunction "2_2") (pintype "passive"))
      (node (ref "C60") (pin "2") (pinfunction "2_2") (pintype "passive"))
      (node (ref "C61") (pin "2") (pinfunction "2_2") (pintype "passive"))
      (node (ref "C62") (pin "2") (pinfunction "2_2") (pintype "passive"))
      (node (ref "C63") (pin "2") (pinfunction "2_2") (pintype "passive"))
      (node (ref "C64") (pin "2") (pinfunction "2_2") (pintype "passive"))
      (node (ref "C65") (pin "2") (pinfunction "2_2") (pintype "passive"))
      (node (ref "C66") (pin "2") (pinfunction "2_2") (pintype "passive"))
      (node (ref "C67") (pin "2") (pinfunction "2_2") (pintype "passive"))
      (node (ref "C68") (pin "2") (pinfunction "2_2") (pintype "passive"))
      (node (ref "C69") (pin "2") (pinfunction "2_2") (pintype "passive"))
      (node (ref "C7") (pin "2") (pinfunction "2_2") (pintype "passive"))
      (node (ref "C70") (pin "2") (pinfunction "2_2") (pintype "passive"))
      (node (ref "C71") (pin "2") (pinfunction "2_2") (pintype "passive"))
      (node (ref "C72") (pin "2") (pinfunction "2_2") (pintype "passive"))
      (node (ref "C73") (pin "2") (pinfunction "2_2") (pintype "passive"))
      (node (ref "C74") (pin "2") (pinfunction "2_2") (pintype "passive"))
      (node (ref "C75") (pin "2") (pinfunction "2_2") (pintype "passive"))
      (node (ref "C76") (pin "2") (pinfunction "2_2") (pintype "passive"))
      (node (ref "C77") (pin "2") (pinfunction "2_2") (pintype "passive"))
      (node (ref "C78") (pin "2") (pinfunction "2_2") (pintype "passive"))
      (node (ref "C79") (pin "2") (pinfunction "2_2") (pintype "passive"))
      (node (ref "C8") (pin "2") (pinfunction "2_2") (pintype "passive"))
      (node (ref "C80") (pin "2") (pinfunction "2_2") (pintype "passive"))
      (node (ref "C81") (pin "2") (pinfunction "2_2") (pintype "passive"))
      (node (ref "C82") (pin "2") (pinfunction "2_2") (pintype "passive"))
      (node (ref "C83") (pin "2") (pinfunction "2_2") (pintype "passive"))
      (node (ref "C84") (pin "2") (pinfunction "2_2") (pintype "passive"))
      (node (ref "C85") (pin "2") (pinfunction "2_2") (pintype "passive"))
      (node (ref "C86") (pin "2") (pinfunction "2_2") (pintype "passive"))
      (node (ref "C87") (pin "2") (pinfunction "2_2") (pintype "passive"))
      (node (ref "C88") (pin "2") (pinfunction "2_2") (pintype "passive"))
      (node (ref "C89") (pin "2") (pinfunction "2_2") (pintype "passive"))
      (node (ref "C9") (pin "2") (pinfunction "2_2") (pintype "passive"))
      (node (ref "C90") (pin "2") (pinfunction "2_2") (pintype "passive"))
      (node (ref "C91") (pin "1") (pinfunction "1_1") (pintype "passive"))
      (node (ref "C92") (pin "2") (pinfunction "2_2") (pintype "passive"))
      (node (ref "C93") (pin "2") (pinfunction "2_2") (pintype "passive"))
      (node (ref "GND") (pin "TP") (pinfunction "TP_TP") (pintype "input"))
      (node (ref "GND75") (pin "TP") (pinfunction "TP_TP") (pintype "input"))
      (node (ref "GND77") (pin "TP") (pinfunction "TP_TP") (pintype "input"))
      (node (ref "R12") (pin "2") (pinfunction "2_2") (pintype "passive"))
      (node (ref "R15") (pin "2") (pinfunction "2_2") (pintype "passive"))
      (node (ref "R18") (pin "2") (pinfunction "2_2") (pintype "passive"))
      (node (ref "R22") (pin "1") (pinfunction "1_1") (pintype "passive"))
      (node (ref "R2X") (pin "2") (pinfunction "2_2") (pintype "passive"))
      (node (ref "R3") (pin "2") (pinfunction "2_2") (pintype "passive"))
      (node (ref "R6") (pin "2") (pinfunction "2_2") (pintype "passive"))
      (node (ref "R9") (pin "2") (pinfunction "2_2") (pintype "passive"))
      (node (ref "SENSOR") (pin "A21") (pinfunction "GND_A21") (pintype "power_in"))
      (node (ref "SENSOR") (pin "A25") (pinfunction "GND_A25") (pintype "power_in"))
      (node (ref "SENSOR") (pin "A28") (pinfunction "GND_A28") (pintype "power_in"))
      (node (ref "SENSOR") (pin "A29") (pinfunction "GND_A29") (pintype "power_in"))
      (node (ref "SENSOR") (pin "A9") (pinfunction "GND_A9") (pintype "power_in"))
      (node (ref "SENSOR") (pin "B22") (pinfunction "GND_B22") (pintype "power_in"))
      (node (ref "SENSOR") (pin "B26") (pinfunction "GND_B26") (pintype "power_in"))
      (node (ref "SENSOR") (pin "B27") (pinfunction "GND_B27") (pintype "power_in"))
      (node (ref "SENSOR") (pin "B28") (pinfunction "GND_B28") (pintype "power_in"))
      (node (ref "SENSOR") (pin "B5") (pinfunction "GND_B5") (pintype "power_in"))
      (node (ref "SENSOR") (pin "C15") (pinfunction "GND_C15") (pintype "power_in"))
      (node (ref "SENSOR") (pin "C16") (pinfunction "GND_C16") (pintype "power_in"))
      (node (ref "SENSOR") (pin "C28") (pinfunction "GND_C28") (pintype "power_in"))
      (node (ref "SENSOR") (pin "D2") (pinfunction "GND_D2") (pintype "power_in"))
      (node (ref "SENSOR") (pin "D25") (pinfunction "GND_D25") (pintype "power_in"))
      (node (ref "SENSOR") (pin "D27") (pinfunction "GND_D27") (pintype "power_in"))
      (node (ref "SENSOR") (pin "D29") (pinfunction "GND_D29") (pintype "power_in"))
      (node (ref "SENSOR") (pin "E15") (pinfunction "GND_E15") (pintype "power_in"))
      (node (ref "SENSOR") (pin "E16") (pinfunction "GND_E16") (pintype "power_in"))
      (node (ref "SENSOR") (pin "E25") (pinfunction "GND_E25") (pintype "power_in"))
      (node (ref "SENSOR") (pin "E27") (pinfunction "GND_E27") (pintype "power_in"))
      (node (ref "SENSOR") (pin "E3") (pinfunction "GND_E3") (pintype "power_in"))
      (node (ref "SENSOR") (pin "E4") (pinfunction "DIO2_E4") (pintype "output"))
      (node (ref "SENSOR") (pin "F27") (pinfunction "GND_F27") (pintype "power_in"))
      (node (ref "SENSOR") (pin "F4") (pinfunction "DIO1_F4") (pintype "output"))
      (node (ref "SENSOR") (pin "G3") (pinfunction "DIO4_G3") (pintype "output"))
      (node (ref "SENSOR") (pin "G5") (pinfunction "GND_G5") (pintype "power_in"))
      (node (ref "SENSOR") (pin "H1") (pinfunction "GND_H1") (pintype "power_in"))
      (node (ref "SENSOR") (pin "H21") (pinfunction "GND_H21") (pintype "power_in"))
      (node (ref "SENSOR") (pin "H25") (pinfunction "GND_H25") (pintype "power_in"))
      (node (ref "SENSOR") (pin "H27") (pinfunction "GND_H27") (pintype "power_in"))
      (node (ref "SENSOR") (pin "H4") (pinfunction "DIO3_H4") (pintype "output"))
      (node (ref "SENSOR") (pin "H6") (pinfunction "GND_H6") (pintype "power_in"))
      (node (ref "SENSOR") (pin "H9") (pinfunction "GND_H9") (pintype "power_in"))
      (node (ref "U1") (pin "6") (pinfunction "ANODE_6") (pintype "input"))
      (node (ref "U2") (pin "6") (pinfunction "ANODE_6") (pintype "input"))
      (node (ref "U3") (pin "2") (pinfunction "GND_2") (pintype "power_in"))
      (node (ref "U3") (pin "EP") (pinfunction "EP_EP") (pintype "power_in"))
      (node (ref "U4") (pin "16") (pinfunction "DIR2_16") (pintype "input"))
      (node (ref "U4") (pin "7") (pinfunction "~{OE}_7") (pintype "input"))
      (node (ref "U4") (pin "8") (pinfunction "GND_8") (pintype "passive"))
      (node (ref "U5") (pin "6") (pinfunction "DIR4_6") (pintype "input"))
      (node (ref "U5") (pin "7") (pinfunction "~{OE}_7") (pintype "input"))
      (node (ref "U5") (pin "8") (pinfunction "GND_8") (pintype "passive"))
      (node (ref "U6") (pin "16") (pinfunction "DIR2_16") (pintype "input"))
      (node (ref "U6") (pin "7") (pinfunction "~{OE}_7") (pintype "input"))
      (node (ref "U6") (pin "8") (pinfunction "GND_8") (pintype "passive"))
      (node (ref "U7") (pin "4") (pinfunction "GND_4") (pintype "power_in"))
      (node (ref "U7") (pin "5") (pinfunction "A2_5") (pintype "input"))
      (node (ref "U7") (pin "6") (pinfunction "A1_6") (pintype "input"))
      (node (ref "U7") (pin "7") (pinfunction "A0_7") (pintype "input"))
      (node (ref "UEP") (pin "1") (pinfunction "A0_1") (pintype "input"))
      (node (ref "UEP") (pin "2") (pinfunction "A1_2") (pintype "input"))
      (node (ref "UEP") (pin "3") (pinfunction "A2_3") (pintype "input"))
      (node (ref "UEP") (pin "4") (pinfunction "GND_4") (pintype "passive"))
      (node (ref "UEP") (pin "EP") (pinfunction "EP_EP") (pintype "passive"))
      (node (ref "UNE") (pin "4") (pinfunction "VSS_4") (pintype "power_in"))
      (node (ref "UNE") (pin "EP") (pinfunction "EP_EP") (pintype "passive"))
      (node (ref "UNN") (pin "4") (pinfunction "VSS_4") (pintype "power_in"))
      (node (ref "UNN") (pin "EP") (pinfunction "EP_EP") (pintype "passive"))
      (node (ref "UNW") (pin "4") (pinfunction "VSS_4") (pintype "power_in"))
      (node (ref "UNW") (pin "EP") (pinfunction "EP_EP") (pintype "passive"))
      (node (ref "USE") (pin "4") (pinfunction "VSS_4") (pintype "power_in"))
      (node (ref "USE") (pin "EP") (pinfunction "EP_EP") (pintype "passive"))
      (node (ref "USS") (pin "4") (pinfunction "VSS_4") (pintype "power_in"))
      (node (ref "USS") (pin "EP") (pinfunction "EP_EP") (pintype "passive"))
      (node (ref "USW") (pin "4") (pinfunction "VSS_4") (pintype "power_in"))
      (node (ref "USW") (pin "EP") (pinfunction "EP_EP") (pintype "passive"))
      (node (ref "X-NORTH") (pin "102") (pinfunction "102_102") (pintype "bidirectional"))
      (node (ref "X-NORTH") (pin "103") (pinfunction "103_103") (pintype "bidirectional"))
      (node (ref "X-NORTH") (pin "108") (pinfunction "108_108") (pintype "bidirectional"))
      (node (ref "X-NORTH") (pin "114") (pinfunction "114_114") (pintype "bidirectional"))
      (node (ref "X-NORTH") (pin "12") (pinfunction "12_12") (pintype "bidirectional"))
      (node (ref "X-NORTH") (pin "120") (pinfunction "120_120") (pintype "bidirectional"))
      (node (ref "X-NORTH") (pin "126") (pinfunction "126_126") (pintype "bidirectional"))
      (node (ref "X-NORTH") (pin "132") (pinfunction "132_132") (pintype "bidirectional"))
      (node (ref "X-NORTH") (pin "138") (pinfunction "138_138") (pintype "bidirectional"))
      (node (ref "X-NORTH") (pin "139") (pinfunction "139_139") (pintype "bidirectional"))
      (node (ref "X-NORTH") (pin "18") (pinfunction "18_18") (pintype "bidirectional"))
      (node (ref "X-NORTH") (pin "24") (pinfunction "24_24") (pintype "bidirectional"))
      (node (ref "X-NORTH") (pin "30") (pinfunction "30_30") (pintype "bidirectional"))
      (node (ref "X-NORTH") (pin "36") (pinfunction "36_36") (pintype "bidirectional"))
      (node (ref "X-NORTH") (pin "42") (pinfunction "42_42") (pintype "bidirectional"))
      (node (ref "X-NORTH") (pin "43") (pinfunction "43_43") (pintype "bidirectional"))
      (node (ref "X-NORTH") (pin "48") (pinfunction "48_48") (pintype "bidirectional"))
      (node (ref "X-NORTH") (pin "54") (pinfunction "54_54") (pintype "bidirectional"))
      (node (ref "X-NORTH") (pin "60") (pinfunction "60_60") (pintype "bidirectional"))
      (node (ref "X-NORTH") (pin "66") (pinfunction "66_66") (pintype "bidirectional"))
      (node (ref "X-NORTH") (pin "72") (pinfunction "72_72") (pintype "bidirectional"))
      (node (ref "X-NORTH") (pin "78") (pinfunction "78_78") (pintype "bidirectional"))
      (node (ref "X-NORTH") (pin "84") (pinfunction "84_84") (pintype "bidirectional"))
      (node (ref "X-NORTH") (pin "90") (pinfunction "90_90") (pintype "bidirectional"))
      (node (ref "X-NORTH") (pin "96") (pinfunction "96_96") (pintype "bidirectional"))
      (node (ref "X-SOUTH") (pin "102") (pinfunction "102_102") (pintype "bidirectional"))
      (node (ref "X-SOUTH") (pin "103") (pinfunction "103_103") (pintype "bidirectional"))
      (node (ref "X-SOUTH") (pin "108") (pinfunction "108_108") (pintype "bidirectional"))
      (node (ref "X-SOUTH") (pin "114") (pinfunction "114_114") (pintype "bidirectional"))
      (node (ref "X-SOUTH") (pin "12") (pinfunction "12_12") (pintype "bidirectional"))
      (node (ref "X-SOUTH") (pin "120") (pinfunction "120_120") (pintype "bidirectional"))
      (node (ref "X-SOUTH") (pin "126") (pinfunction "126_126") (pintype "bidirectional"))
      (node (ref "X-SOUTH") (pin "132") (pinfunction "132_132") (pintype "bidirectional"))
      (node (ref "X-SOUTH") (pin "138") (pinfunction "138_138") (pintype "bidirectional"))
      (node (ref "X-SOUTH") (pin "139") (pinfunction "139_139") (pintype "bidirectional"))
      (node (ref "X-SOUTH") (pin "18") (pinfunction "18_18") (pintype "bidirectional"))
      (node (ref "X-SOUTH") (pin "24") (pinfunction "24_24") (pintype "bidirectional"))
      (node (ref "X-SOUTH") (pin "30") (pinfunction "30_30") (pintype "bidirectional"))
      (node (ref "X-SOUTH") (pin "36") (pinfunction "36_36") (pintype "bidirectional"))
      (node (ref "X-SOUTH") (pin "42") (pinfunction "42_42") (pintype "bidirectional"))
      (node (ref "X-SOUTH") (pin "43") (pinfunction "43_43") (pintype "bidirectional"))
      (node (ref "X-SOUTH") (pin "48") (pinfunction "48_48") (pintype "bidirectional"))
      (node (ref "X-SOUTH") (pin "54") (pinfunction "54_54") (pintype "bidirectional"))
      (node (ref "X-SOUTH") (pin "60") (pinfunction "60_60") (pintype "bidirectional"))
      (node (ref "X-SOUTH") (pin "66") (pinfunction "66_66") (pintype "bidirectional"))
      (node (ref "X-SOUTH") (pin "72") (pinfunction "72_72") (pintype "bidirectional"))
      (node (ref "X-SOUTH") (pin "78") (pinfunction "78_78") (pintype "bidirectional"))
      (node (ref "X-SOUTH") (pin "84") (pinfunction "84_84") (pintype "bidirectional"))
      (node (ref "X-SOUTH") (pin "90") (pinfunction "90_90") (pintype "bidirectional"))
      (node (ref "X-SOUTH") (pin "96") (pinfunction "96_96") (pintype "bidirectional"))
    )
    (net (code "4") (name "N$42") (class "Default")
      (node (ref "SENSOR") (pin "A2") (pinfunction "TANA_A2") (pintype "output"))
    )
    (net (code "5") (name "N00_N") (class "Default")
      (node (ref "R25") (pin "2") (pinfunction "2_2") (pintype "passive"))
      (node (ref "SENSOR") (pin "E6") (pinfunction "LVDS_CLK_P_E6") (pintype "input"))
      (node (ref "X-NORTH") (pin "16") (pinfunction "16_16") (pintype "bidirectional"))
    )
    (net (code "6") (name "N00_P") (class "Default")
      (node (ref "R25") (pin "1") (pinfunction "1_1") (pintype "passive"))
      (node (ref "SENSOR") (pin "E5") (pinfunction "LVDS_CLK_N_E5") (pintype "input"))
      (node (ref "X-NORTH") (pin "14") (pinfunction "14_14") (pintype "bidirectional"))
    )
    (net (code "7") (name "N01_N") (class "Default")
      (node (ref "SENSOR") (pin "G7") (pinfunction "OUTCLK_P_G7") (pintype "output"))
      (node (ref "X-NORTH") (pin "17") (pinfunction "17_17") (pintype "bidirectional"))
    )
    (net (code "8") (name "N01_P") (class "Default")
      (node (ref "SENSOR") (pin "G6") (pinfunction "OUTCLK_N_G6") (pintype "output"))
      (node (ref "X-NORTH") (pin "15") (pinfunction "15_15") (pintype "bidirectional"))
    )
    (net (code "9") (name "N02_N") (class "Default")
      (node (ref "SENSOR") (pin "F7") (pinfunction "OUT33_P_F7") (pintype "output"))
      (node (ref "X-NORTH") (pin "22") (pinfunction "22_22") (pintype "bidirectional"))
    )
    (net (code "10") (name "N02_P") (class "Default")
      (node (ref "SENSOR") (pin "F6") (pinfunction "OUT33_N_F6") (pintype "output"))
      (node (ref "X-NORTH") (pin "20") (pinfunction "20_20") (pintype "bidirectional"))
    )
    (net (code "11") (name "N03_N") (class "Default")
      (node (ref "X-NORTH") (pin "23") (pinfunction "23_23") (pintype "bidirectional"))
    )
    (net (code "12") (name "N03_P") (class "Default")
      (node (ref "X-NORTH") (pin "21") (pinfunction "21_21") (pintype "bidirectional"))
    )
    (net (code "13") (name "N04_N") (class "Default")
      (node (ref "SENSOR") (pin "E8") (pinfunction "OUT35_P_E8") (pintype "output"))
      (node (ref "X-NORTH") (pin "28") (pinfunction "28_28") (pintype "bidirectional"))
    )
    (net (code "14") (name "N04_P") (class "Default")
      (node (ref "SENSOR") (pin "E7") (pinfunction "OUT35_N_E7") (pintype "output"))
      (node (ref "X-NORTH") (pin "26") (pinfunction "26_26") (pintype "bidirectional"))
    )
    (net (code "15") (name "N05_N") (class "Default")
      (node (ref "SENSOR") (pin "H8") (pinfunction "OUT34_P_H8") (pintype "output"))
      (node (ref "X-NORTH") (pin "29") (pinfunction "29_29") (pintype "bidirectional"))
    )
    (net (code "16") (name "N05_P") (class "Default")
      (node (ref "SENSOR") (pin "H7") (pinfunction "OUT34_N_H7") (pintype "output"))
      (node (ref "X-NORTH") (pin "27") (pinfunction "27_27") (pintype "bidirectional"))
    )
    (net (code "17") (name "N06_N") (class "Default")
      (node (ref "SENSOR") (pin "F9") (pinfunction "OUT37_P_F9") (pintype "output"))
      (node (ref "X-NORTH") (pin "34") (pinfunction "34_34") (pintype "bidirectional"))
    )
    (net (code "18") (name "N06_P") (class "Default")
      (node (ref "SENSOR") (pin "F8") (pinfunction "OUT37_N_F8") (pintype "output"))
      (node (ref "X-NORTH") (pin "32") (pinfunction "32_32") (pintype "bidirectional"))
    )
    (net (code "19") (name "N07_N") (class "Default")
      (node (ref "SENSOR") (pin "G9") (pinfunction "OUT36_P_G9") (pintype "output"))
      (node (ref "X-NORTH") (pin "35") (pinfunction "35_35") (pintype "bidirectional"))
    )
    (net (code "20") (name "N07_P") (class "Default")
      (node (ref "SENSOR") (pin "G8") (pinfunction "OUT36_N_G8") (pintype "output"))
      (node (ref "X-NORTH") (pin "33") (pinfunction "33_33") (pintype "bidirectional"))
    )
    (net (code "21") (name "N08_N") (class "Default")
      (node (ref "SENSOR") (pin "E10") (pinfunction "OUT38_P_E10") (pintype "output"))
      (node (ref "X-NORTH") (pin "40") (pinfunction "40_40") (pintype "bidirectional"))
    )
    (net (code "22") (name "N08_P") (class "Default")
      (node (ref "SENSOR") (pin "E9") (pinfunction "OUT38_N_E9") (pintype "output"))
      (node (ref "X-NORTH") (pin "38") (pinfunction "38_38") (pintype "bidirectional"))
    )
    (net (code "23") (name "N09_N") (class "Default")
      (node (ref "SENSOR") (pin "G11") (pinfunction "OUT39_P_G11") (pintype "output"))
      (node (ref "X-NORTH") (pin "41") (pinfunction "41_41") (pintype "bidirectional"))
    )
    (net (code "24") (name "N09_P") (class "Default")
      (node (ref "SENSOR") (pin "G10") (pinfunction "OUT39_N_G10") (pintype "output"))
      (node (ref "X-NORTH") (pin "39") (pinfunction "39_39") (pintype "bidirectional"))
    )
    (net (code "25") (name "N10_N") (class "Default")
      (node (ref "SENSOR") (pin "F11") (pinfunction "OUT40_P_F11") (pintype "output"))
      (node (ref "X-NORTH") (pin "46") (pinfunction "46_46") (pintype "bidirectional"))
    )
    (net (code "26") (name "N10_P") (class "Default")
      (node (ref "SENSOR") (pin "F10") (pinfunction "OUT40_N_F10") (pintype "output"))
      (node (ref "X-NORTH") (pin "44") (pinfunction "44_44") (pintype "bidirectional"))
    )
    (net (code "27") (name "N11_N") (class "Default")
      (node (ref "SENSOR") (pin "H12") (pinfunction "OUT41_P_H12") (pintype "output"))
      (node (ref "X-NORTH") (pin "47") (pinfunction "47_47") (pintype "bidirectional"))
    )
    (net (code "28") (name "N11_P") (class "Default")
      (node (ref "SENSOR") (pin "H11") (pinfunction "OUT41_N_H11") (pintype "output"))
      (node (ref "X-NORTH") (pin "45") (pinfunction "45_45") (pintype "bidirectional"))
    )
    (net (code "29") (name "N12_N") (class "Default")
      (node (ref "SENSOR") (pin "E12") (pinfunction "OUT42_P_E12") (pintype "output"))
      (node (ref "X-NORTH") (pin "52") (pinfunction "52_52") (pintype "bidirectional"))
    )
    (net (code "30") (name "N12_P") (class "Default")
      (node (ref "SENSOR") (pin "E11") (pinfunction "OUT42_N_E11") (pintype "output"))
      (node (ref "X-NORTH") (pin "50") (pinfunction "50_50") (pintype "bidirectional"))
    )
    (net (code "31") (name "N13_N") (class "Default")
      (node (ref "SENSOR") (pin "G13") (pinfunction "OUT43_P_G13") (pintype "output"))
      (node (ref "X-NORTH") (pin "53") (pinfunction "53_53") (pintype "bidirectional"))
    )
    (net (code "32") (name "N13_P") (class "Default")
      (node (ref "SENSOR") (pin "G12") (pinfunction "OUT43_N_G12") (pintype "output"))
      (node (ref "X-NORTH") (pin "51") (pinfunction "51_51") (pintype "bidirectional"))
    )
    (net (code "33") (name "N14_N") (class "Default")
      (node (ref "SENSOR") (pin "F13") (pinfunction "OUT44_P_F13") (pintype "output"))
      (node (ref "X-NORTH") (pin "58") (pinfunction "58_58") (pintype "bidirectional"))
    )
    (net (code "34") (name "N14_P") (class "Default")
      (node (ref "SENSOR") (pin "F12") (pinfunction "OUT44_N_F12") (pintype "output"))
      (node (ref "X-NORTH") (pin "56") (pinfunction "56_56") (pintype "bidirectional"))
    )
    (net (code "35") (name "N15_N") (class "Default")
      (node (ref "SENSOR") (pin "H14") (pinfunction "OUT45_P_H14") (pintype "output"))
      (node (ref "X-NORTH") (pin "59") (pinfunction "59_59") (pintype "bidirectional"))
    )
    (net (code "36") (name "N15_P") (class "Default")
      (node (ref "SENSOR") (pin "H13") (pinfunction "OUT45_N_H13") (pintype "output"))
      (node (ref "X-NORTH") (pin "57") (pinfunction "57_57") (pintype "bidirectional"))
    )
    (net (code "37") (name "N16_N") (class "Default")
      (node (ref "SENSOR") (pin "E14") (pinfunction "OUT46_P_E14") (pintype "output"))
      (node (ref "X-NORTH") (pin "64") (pinfunction "64_64") (pintype "bidirectional"))
    )
    (net (code "38") (name "N16_P") (class "Default")
      (node (ref "SENSOR") (pin "E13") (pinfunction "OUT46_N_E13") (pintype "output"))
      (node (ref "X-NORTH") (pin "62") (pinfunction "62_62") (pintype "bidirectional"))
    )
    (net (code "39") (name "N17_N") (class "Default")
      (node (ref "SENSOR") (pin "G15") (pinfunction "OUT47_P_G15") (pintype "output"))
      (node (ref "X-NORTH") (pin "65") (pinfunction "65_65") (pintype "bidirectional"))
    )
    (net (code "40") (name "N17_P") (class "Default")
      (node (ref "SENSOR") (pin "G14") (pinfunction "OUT47_N_G14") (pintype "output"))
      (node (ref "X-NORTH") (pin "63") (pinfunction "63_63") (pintype "bidirectional"))
    )
    (net (code "41") (name "N18_N") (class "Default")
      (node (ref "SENSOR") (pin "F15") (pinfunction "OUT48_P_F15") (pintype "output"))
      (node (ref "X-NORTH") (pin "70") (pinfunction "70_70") (pintype "bidirectional"))
    )
    (net (code "42") (name "N18_P") (class "Default")
      (node (ref "SENSOR") (pin "F14") (pinfunction "OUT48_N_F14") (pintype "output"))
      (node (ref "X-NORTH") (pin "68") (pinfunction "68_68") (pintype "bidirectional"))
    )
    (net (code "43") (name "N19_N") (class "Default")
      (node (ref "SENSOR") (pin "G17") (pinfunction "OUT50_P_G17") (pintype "output"))
      (node (ref "X-NORTH") (pin "71") (pinfunction "71_71") (pintype "bidirectional"))
    )
    (net (code "44") (name "N19_P") (class "Default")
      (node (ref "SENSOR") (pin "G16") (pinfunction "OUT50_N_G16") (pintype "output"))
      (node (ref "X-NORTH") (pin "69") (pinfunction "69_69") (pintype "bidirectional"))
    )
    (net (code "45") (name "N20_N") (class "Default")
      (node (ref "SENSOR") (pin "F17") (pinfunction "OUT49_P_F17") (pintype "output"))
      (node (ref "X-NORTH") (pin "76") (pinfunction "76_76") (pintype "bidirectional"))
    )
    (net (code "46") (name "N20_P") (class "Default")
      (node (ref "SENSOR") (pin "F16") (pinfunction "OUT49_N_F16") (pintype "output"))
      (node (ref "X-NORTH") (pin "74") (pinfunction "74_74") (pintype "bidirectional"))
    )
    (net (code "47") (name "N21_N") (class "Default")
      (node (ref "SENSOR") (pin "H18") (pinfunction "OUT52_P_H18") (pintype "output"))
      (node (ref "X-NORTH") (pin "77") (pinfunction "77_77") (pintype "bidirectional"))
    )
    (net (code "48") (name "N21_P") (class "Default")
      (node (ref "SENSOR") (pin "H17") (pinfunction "OUT52_N_H17") (pintype "output"))
      (node (ref "X-NORTH") (pin "75") (pinfunction "75_75") (pintype "bidirectional"))
    )
    (net (code "49") (name "N22_N") (class "Default")
      (node (ref "SENSOR") (pin "E18") (pinfunction "OUT51_P_E18") (pintype "output"))
      (node (ref "X-NORTH") (pin "82") (pinfunction "82_82") (pintype "bidirectional"))
    )
    (net (code "50") (name "N22_P") (class "Default")
      (node (ref "SENSOR") (pin "E17") (pinfunction "OUT51_N_E17") (pintype "output"))
      (node (ref "X-NORTH") (pin "80") (pinfunction "80_80") (pintype "bidirectional"))
    )
    (net (code "51") (name "N23_N") (class "Default")
      (node (ref "SENSOR") (pin "G19") (pinfunction "OUT54_P_G19") (pintype "output"))
      (node (ref "X-NORTH") (pin "83") (pinfunction "83_83") (pintype "bidirectional"))
    )
    (net (code "52") (name "N23_P") (class "Default")
      (node (ref "SENSOR") (pin "G18") (pinfunction "OUT54_N_G18") (pintype "output"))
      (node (ref "X-NORTH") (pin "81") (pinfunction "81_81") (pintype "bidirectional"))
    )
    (net (code "53") (name "N24_N") (class "Default")
      (node (ref "SENSOR") (pin "F19") (pinfunction "OUT53_P_F19") (pintype "output"))
      (node (ref "X-NORTH") (pin "88") (pinfunction "88_88") (pintype "bidirectional"))
    )
    (net (code "54") (name "N24_P") (class "Default")
      (node (ref "SENSOR") (pin "F18") (pinfunction "OUT53_N_F18") (pintype "output"))
      (node (ref "X-NORTH") (pin "86") (pinfunction "86_86") (pintype "bidirectional"))
    )
    (net (code "55") (name "N25_N") (class "Default")
      (node (ref "SENSOR") (pin "H20") (pinfunction "OUT56_P_H20") (pintype "output"))
      (node (ref "X-NORTH") (pin "89") (pinfunction "89_89") (pintype "bidirectional"))
    )
    (net (code "56") (name "N25_P") (class "Default")
      (node (ref "SENSOR") (pin "H19") (pinfunction "OUT56_N_H19") (pintype "output"))
      (node (ref "X-NORTH") (pin "87") (pinfunction "87_87") (pintype "bidirectional"))
    )
    (net (code "57") (name "N26_N") (class "Default")
      (node (ref "SENSOR") (pin "E20") (pinfunction "OUT55_P_E20") (pintype "output"))
      (node (ref "X-NORTH") (pin "94") (pinfunction "94_94") (pintype "bidirectional"))
    )
    (net (code "58") (name "N26_P") (class "Default")
      (node (ref "SENSOR") (pin "E19") (pinfunction "OUT55_N_E19") (pintype "output"))
      (node (ref "X-NORTH") (pin "92") (pinfunction "92_92") (pintype "bidirectional"))
    )
    (net (code "59") (name "N27_N") (class "Default")
      (node (ref "SENSOR") (pin "G21") (pinfunction "OUT58_P_G21") (pintype "output"))
      (node (ref "X-NORTH") (pin "95") (pinfunction "95_95") (pintype "bidirectional"))
    )
    (net (code "60") (name "N27_P") (class "Default")
      (node (ref "SENSOR") (pin "G20") (pinfunction "OUT58_N_G20") (pintype "output"))
      (node (ref "X-NORTH") (pin "93") (pinfunction "93_93") (pintype "bidirectional"))
    )
    (net (code "61") (name "N28_N") (class "Default")
      (node (ref "SENSOR") (pin "F21") (pinfunction "OUT57_P_F21") (pintype "output"))
      (node (ref "X-NORTH") (pin "100") (pinfunction "100_100") (pintype "bidirectional"))
    )
    (net (code "62") (name "N28_P") (class "Default")
      (node (ref "SENSOR") (pin "F20") (pinfunction "OUT57_N_F20") (pintype "output"))
      (node (ref "X-NORTH") (pin "98") (pinfunction "98_98") (pintype "bidirectional"))
    )
    (net (code "63") (name "N29_N") (class "Default")
      (node (ref "SENSOR") (pin "G23") (pinfunction "OUT61_P_G23") (pintype "output"))
      (node (ref "X-NORTH") (pin "101") (pinfunction "101_101") (pintype "bidirectional"))
    )
    (net (code "64") (name "N29_P") (class "Default")
      (node (ref "SENSOR") (pin "G22") (pinfunction "OUT61_N_G22") (pintype "output"))
      (node (ref "X-NORTH") (pin "99") (pinfunction "99_99") (pintype "bidirectional"))
    )
    (net (code "65") (name "N30_N") (class "Default")
      (node (ref "SENSOR") (pin "E22") (pinfunction "OUT59_P_E22") (pintype "output"))
      (node (ref "X-NORTH") (pin "106") (pinfunction "106_106") (pintype "bidirectional"))
    )
    (net (code "66") (name "N30_P") (class "Default")
      (node (ref "SENSOR") (pin "E21") (pinfunction "OUT59_N_E21") (pintype "output"))
      (node (ref "X-NORTH") (pin "104") (pinfunction "104_104") (pintype "bidirectional"))
    )
    (net (code "67") (name "N31_N") (class "Default")
      (node (ref "SENSOR") (pin "H24") (pinfunction "OUT63_P_H24") (pintype "output"))
      (node (ref "X-NORTH") (pin "107") (pinfunction "107_107") (pintype "bidirectional"))
    )
    (net (code "68") (name "N31_P") (class "Default")
      (node (ref "SENSOR") (pin "H23") (pinfunction "OUT63_N_H23") (pintype "output"))
      (node (ref "X-NORTH") (pin "105") (pinfunction "105_105") (pintype "bidirectional"))
    )
    (net (code "69") (name "N32_N") (class "Default")
      (node (ref "SENSOR") (pin "F23") (pinfunction "OUT60_P_F23") (pintype "output"))
      (node (ref "X-NORTH") (pin "112") (pinfunction "112_112") (pintype "bidirectional"))
    )
    (net (code "70") (name "N32_P") (class "Default")
      (node (ref "SENSOR") (pin "F22") (pinfunction "OUT60_N_F22") (pintype "output"))
      (node (ref "X-NORTH") (pin "110") (pinfunction "110_110") (pintype "bidirectional"))
    )
    (net (code "71") (name "N33_N") (class "Default")
      (node (ref "SENSOR") (pin "G25") (pinfunction "OUT64_P_G25") (pintype "output"))
      (node (ref "X-NORTH") (pin "113") (pinfunction "113_113") (pintype "bidirectional"))
    )
    (net (code "72") (name "N33_P") (class "Default")
      (node (ref "SENSOR") (pin "G24") (pinfunction "OUT64_N_G24") (pintype "output"))
      (node (ref "X-NORTH") (pin "111") (pinfunction "111_111") (pintype "bidirectional"))
    )
    (net (code "73") (name "N34_N") (class "Default")
      (node (ref "SENSOR") (pin "E24") (pinfunction "OUT62_P_E24") (pintype "output"))
      (node (ref "X-NORTH") (pin "118") (pinfunction "118_118") (pintype "bidirectional"))
    )
    (net (code "74") (name "N34_P") (class "Default")
      (node (ref "SENSOR") (pin "E23") (pinfunction "OUT62_N_E23") (pintype "output"))
      (node (ref "X-NORTH") (pin "116") (pinfunction "116_116") (pintype "bidirectional"))
    )
    (net (code "75") (name "N35_N") (class "Default")
      (node (ref "U6") (pin "4") (pinfunction "A4_4") (pintype "bidirectional"))
      (node (ref "X-NORTH") (pin "119") (pinfunction "119_119") (pintype "bidirectional"))
    )
    (net (code "76") (name "N35_P") (class "Default")
      (node (ref "U6") (pin "3") (pinfunction "A3_3") (pintype "bidirectional"))
      (node (ref "X-NORTH") (pin "117") (pinfunction "117_117") (pintype "bidirectional"))
    )
    (net (code "77") (name "N36_N") (class "Default")
      (node (ref "X-NORTH") (pin "124") (pinfunction "124_124") (pintype "bidirectional"))
    )
    (net (code "78") (name "N36_P") (class "Default")
      (node (ref "X-NORTH") (pin "122") (pinfunction "122_122") (pintype "bidirectional"))
    )
    (net (code "79") (name "N37_N") (class "Default")
      (node (ref "U5") (pin "3") (pinfunction "A3_3") (pintype "bidirectional"))
      (node (ref "X-NORTH") (pin "125") (pinfunction "125_125") (pintype "bidirectional"))
    )
    (net (code "80") (name "N37_P") (class "Default")
      (node (ref "U5") (pin "4") (pinfunction "A4_4") (pintype "bidirectional"))
      (node (ref "X-NORTH") (pin "123") (pinfunction "123_123") (pintype "bidirectional"))
    )
    (net (code "81") (name "N38_N") (class "Default")
      (node (ref "U6") (pin "2") (pinfunction "A2_2") (pintype "bidirectional"))
      (node (ref "X-NORTH") (pin "130") (pinfunction "130_130") (pintype "bidirectional"))
    )
    (net (code "82") (name "N38_P") (class "Default")
      (node (ref "U6") (pin "1") (pinfunction "A1_1") (pintype "bidirectional"))
      (node (ref "X-NORTH") (pin "128") (pinfunction "128_128") (pintype "bidirectional"))
    )
    (net (code "83") (name "N39_N") (class "Default")
      (node (ref "U5") (pin "1") (pinfunction "A1_1") (pintype "bidirectional"))
      (node (ref "X-NORTH") (pin "131") (pinfunction "131_131") (pintype "bidirectional"))
    )
    (net (code "84") (name "N39_P") (class "Default")
      (node (ref "U5") (pin "2") (pinfunction "A2_2") (pintype "bidirectional"))
      (node (ref "X-NORTH") (pin "129") (pinfunction "129_129") (pintype "bidirectional"))
    )
    (net (code "85") (name "N_CHK_EN") (class "Default")
      (node (ref "X-NORTH") (pin "8") (pinfunction "8_8") (pintype "bidirectional"))
    )
    (net (code "86") (name "N_CHK_V") (class "Default")
      (node (ref "C2") (pin "1") (pinfunction "1_1") (pintype "passive"))
      (node (ref "C3") (pin "1") (pinfunction "1_1") (pintype "passive"))
      (node (ref "C4") (pin "1") (pinfunction "1_1") (pintype "passive"))
      (node (ref "R19") (pin "1") (pinfunction "1_1") (pintype "passive"))
      (node (ref "TP1") (pin "TP") (pinfunction "TP_TP") (pintype "input"))
      (node (ref "UNE") (pin "8") (pinfunction "VDD_8") (pintype "power_in"))
      (node (ref "UNN") (pin "8") (pinfunction "VDD_8") (pintype "power_in"))
      (node (ref "UNW") (pin "8") (pinfunction "VDD_8") (pintype "power_in"))
      (node (ref "X-NORTH") (pin "10") (pinfunction "10_10") (pintype "bidirectional"))
    )
    (net (code "87") (name "N_I2C_EN") (class "Default")
      (node (ref "X-NORTH") (pin "137") (pinfunction "137_137") (pintype "bidirectional"))
    )
    (net (code "88") (name "N_I2C_V") (class "Default")
      (node (ref "C1") (pin "1") (pinfunction "1_1") (pintype "passive"))
      (node (ref "R1X") (pin "1") (pinfunction "1_1") (pintype "passive"))
      (node (ref "UEP") (pin "8") (pinfunction "VCC_8") (pintype "power_in"))
      (node (ref "X-NORTH") (pin "135") (pinfunction "135_135") (pintype "bidirectional"))
    )
    (net (code "89") (name "N_REF") (class "Default")
      (node (ref "R19") (pin "2") (pinfunction "2_2") (pintype "passive"))
      (node (ref "TP2") (pin "TP") (pinfunction "TP_TP") (pintype "input"))
      (node (ref "U1") (pin "1") (pinfunction "CATHODE_1") (pintype "output"))
      (node (ref "U1") (pin "3") (pinfunction "REF_3") (pintype "input"))
      (node (ref "UNE") (pin "2") (pinfunction "VINA-_2") (pintype "input"))
      (node (ref "UNE") (pin "5") (pinfunction "VINB+_5") (pintype "input"))
      (node (ref "UNN") (pin "2") (pinfunction "VINA-_2") (pintype "input"))
      (node (ref "UNN") (pin "5") (pinfunction "VINB+_5") (pintype "input"))
      (node (ref "UNW") (pin "2") (pinfunction "VINA-_2") (pintype "input"))
      (node (ref "UNW") (pin "5") (pinfunction "VINB+_5") (pintype "input"))
    )
    (net (code "90") (name "N_SCK") (class "Default")
      (node (ref "U4") (pin "4") (pinfunction "A4_4") (pintype "bidirectional"))
      (node (ref "X-NORTH") (pin "144") (pinfunction "144_144") (pintype "bidirectional"))
    )
    (net (code "91") (name "N_SCL") (class "Default")
      (node (ref "UEP") (pin "6") (pinfunction "SCL_6") (pintype "input"))
      (node (ref "X-NORTH") (pin "143") (pinfunction "143_143") (pintype "bidirectional"))
    )
    (net (code "92") (name "N_SDA") (class "Default")
      (node (ref "UEP") (pin "5") (pinfunction "SDA_5") (pintype "bidirectional"))
      (node (ref "X-NORTH") (pin "141") (pinfunction "141_141") (pintype "bidirectional"))
    )
    (net (code "93") (name "N_SDI") (class "Default")
      (node (ref "U4") (pin "2") (pinfunction "A2_2") (pintype "bidirectional"))
      (node (ref "X-NORTH") (pin "140") (pinfunction "140_140") (pintype "bidirectional"))
    )
    (net (code "94") (name "N_SDO") (class "Default")
      (node (ref "U4") (pin "3") (pinfunction "A3_3") (pintype "bidirectional"))
      (node (ref "X-NORTH") (pin "142") (pinfunction "142_142") (pintype "bidirectional"))
    )
    (net (code "95") (name "N_SPI_EN") (class "Default")
      (node (ref "U4") (pin "1") (pinfunction "A1_1") (pintype "bidirectional"))
      (node (ref "X-NORTH") (pin "136") (pinfunction "136_136") (pintype "bidirectional"))
    )
    (net (code "96") (name "N_SPI_V") (class "Default")
      (node (ref "C59") (pin "1") (pinfunction "1_1") (pintype "passive"))
      (node (ref "U4") (pin "14") (pinfunction "VCCA_14") (pintype "power_in"))
      (node (ref "U4") (pin "15") (pinfunction "DIR1_15") (pintype "input"))
      (node (ref "U4") (pin "5") (pinfunction "DIR3_5") (pintype "input"))
      (node (ref "U4") (pin "6") (pinfunction "DIR4_6") (pintype "input"))
      (node (ref "X-NORTH") (pin "134") (pinfunction "134_134") (pintype "bidirectional"))
    )
    (net (code "97") (name "N_VE") (class "Default")
      (node (ref "C22") (pin "1") (pinfunction "1_1") (pintype "passive"))
      (node (ref "C23") (pin "1") (pinfunction "1_1") (pintype "passive"))
      (node (ref "C24") (pin "1") (pinfunction "1_1") (pintype "passive"))
      (node (ref "C25") (pin "1") (pinfunction "1_1") (pintype "passive"))
      (node (ref "C26") (pin "1") (pinfunction "1_1") (pintype "passive"))
      (node (ref "C27") (pin "1") (pinfunction "1_1") (pintype "passive"))
      (node (ref "C28") (pin "1") (pinfunction "1_1") (pintype "passive"))
      (node (ref "C50") (pin "1") (pinfunction "1_1") (pintype "passive"))
      (node (ref "C51") (pin "1") (pinfunction "1_1") (pintype "passive"))
      (node (ref "C52") (pin "1") (pinfunction "1_1") (pintype "passive"))
      (node (ref "C53") (pin "1") (pinfunction "1_1") (pintype "passive"))
      (node (ref "C54") (pin "1") (pinfunction "1_1") (pintype "passive"))
      (node (ref "C55") (pin "1") (pinfunction "1_1") (pintype "passive"))
      (node (ref "C56") (pin "1") (pinfunction "1_1") (pintype "passive"))
      (node (ref "C67") (pin "1") (pinfunction "1_1") (pintype "passive"))
      (node (ref "C69") (pin "1") (pinfunction "1_1") (pintype "passive"))
      (node (ref "C75") (pin "1") (pinfunction "1_1") (pintype "passive"))
      (node (ref "C76") (pin "1") (pinfunction "1_1") (pintype "passive"))
      (node (ref "C77") (pin "1") (pinfunction "1_1") (pintype "passive"))
      (node (ref "C84") (pin "1") (pinfunction "1_1") (pintype "passive"))
      (node (ref "C85") (pin "1") (pinfunction "1_1") (pintype "passive"))
      (node (ref "C86") (pin "1") (pinfunction "1_1") (pintype "passive"))
      (node (ref "C93") (pin "1") (pinfunction "1_1") (pintype "passive"))
      (node (ref "SENSOR") (pin "C26") (pinfunction "VDD33_C26") (pintype "power_in"))
      (node (ref "SENSOR") (pin "C27") (pinfunction "VDD33_C27") (pintype "power_in"))
      (node (ref "SENSOR") (pin "D26") (pinfunction "VDD33_D26") (pintype "power_in"))
      (node (ref "SENSOR") (pin "D3") (pinfunction "VDD33_D3") (pintype "power_in"))
      (node (ref "SENSOR") (pin "E26") (pinfunction "VDD33_E26") (pintype "power_in"))
      (node (ref "SENSOR") (pin "F26") (pinfunction "VDD33_F26") (pintype "power_in"))
      (node (ref "SENSOR") (pin "F5") (pinfunction "VDD33_F5") (pintype "power_in"))
      (node (ref "TP7") (pin "TP") (pinfunction "TP_TP") (pintype "input"))
      (node (ref "U4") (pin "13") (pinfunction "VCCB_13") (pintype "power_in"))
      (node (ref "U5") (pin "13") (pinfunction "VCCB_13") (pintype "power_in"))
      (node (ref "U6") (pin "13") (pinfunction "VCCB_13") (pintype "power_in"))
      (node (ref "X-NORTH") (pin "109") (pinfunction "109_109") (pintype "bidirectional"))
      (node (ref "X-NORTH") (pin "115") (pinfunction "115_115") (pintype "bidirectional"))
      (node (ref "X-NORTH") (pin "121") (pinfunction "121_121") (pintype "bidirectional"))
      (node (ref "X-NORTH") (pin "127") (pinfunction "127_127") (pintype "bidirectional"))
      (node (ref "X-NORTH") (pin "133") (pinfunction "133_133") (pintype "bidirectional"))
    )
    (net (code "98") (name "N_VE_CV") (class "Default")
      (node (ref "C10") (pin "1") (pinfunction "1_1") (pintype "passive"))
      (node (ref "R7") (pin "1") (pinfunction "1_1") (pintype "passive"))
      (node (ref "X-NORTH") (pin "6") (pinfunction "6_6") (pintype "bidirectional"))
    )
    (net (code "99") (name "N_VE_OV") (class "Default")
      (node (ref "UNE") (pin "7") (pinfunction "OUTB_7") (pintype "output"))
      (node (ref "X-NORTH") (pin "5") (pinfunction "5_5") (pintype "bidirectional"))
    )
    (net (code "100") (name "N_VE_UV") (class "Default")
      (node (ref "UNE") (pin "1") (pinfunction "OUTA_1") (pintype "output"))
      (node (ref "X-NORTH") (pin "11") (pinfunction "11_11") (pintype "bidirectional"))
    )
    (net (code "101") (name "N_VN") (class "Default")
      (node (ref "C31") (pin "1") (pinfunction "1_1") (pintype "passive"))
      (node (ref "C32") (pin "1") (pinfunction "1_1") (pintype "passive"))
      (node (ref "C33") (pin "1") (pinfunction "1_1") (pintype "passive"))
      (node (ref "C34") (pin "1") (pinfunction "1_1") (pintype "passive"))
      (node (ref "C35") (pin "1") (pinfunction "1_1") (pintype "passive"))
      (node (ref "C36") (pin "1") (pinfunction "1_1") (pintype "passive"))
      (node (ref "C37") (pin "1") (pinfunction "1_1") (pintype "passive"))
      (node (ref "C38") (pin "1") (pinfunction "1_1") (pintype "passive"))
      (node (ref "C39") (pin "1") (pinfunction "1_1") (pintype "passive"))
      (node (ref "C40") (pin "1") (pinfunction "1_1") (pintype "passive"))
      (node (ref "C41") (pin "1") (pinfunction "1_1") (pintype "passive"))
      (node (ref "C42") (pin "1") (pinfunction "1_1") (pintype "passive"))
      (node (ref "C43") (pin "1") (pinfunction "1_1") (pintype "passive"))
      (node (ref "C44") (pin "1") (pinfunction "1_1") (pintype "passive"))
      (node (ref "C68") (pin "1") (pinfunction "1_1") (pintype "passive"))
      (node (ref "C70") (pin "1") (pinfunction "1_1") (pintype "passive"))
      (node (ref "C78") (pin "1") (pinfunction "1_1") (pintype "passive"))
      (node (ref "C79") (pin "1") (pinfunction "1_1") (pintype "passive"))
      (node (ref "C80") (pin "1") (pinfunction "1_1") (pintype "passive"))
      (node (ref "C87") (pin "1") (pinfunction "1_1") (pintype "passive"))
      (node (ref "C88") (pin "1") (pinfunction "1_1") (pintype "passive"))
      (node (ref "C89") (pin "1") (pinfunction "1_1") (pintype "passive"))
      (node (ref "SENSOR") (pin "A10") (pinfunction "VDD18_A10") (pintype "power_in"))
      (node (ref "SENSOR") (pin "A15") (pinfunction "VDD18_A15") (pintype "power_in"))
      (node (ref "SENSOR") (pin "A16") (pinfunction "VDD18_A16") (pintype "power_in"))
      (node (ref "SENSOR") (pin "A22") (pinfunction "VDD18_A22") (pintype "power_in"))
      (node (ref "SENSOR") (pin "A26") (pinfunction "VDD18_A26") (pintype "power_in"))
      (node (ref "SENSOR") (pin "A27") (pinfunction "VDD18_A27") (pintype "power_in"))
      (node (ref "SENSOR") (pin "B4") (pinfunction "VDD18_B4") (pintype "power_in"))
      (node (ref "SENSOR") (pin "E1") (pinfunction "VDD18_PLL_E1") (pintype "power_in"))
      (node (ref "SENSOR") (pin "H10") (pinfunction "VDD18_H10") (pintype "power_in"))
      (node (ref "SENSOR") (pin "H15") (pinfunction "VDD18_H15") (pintype "power_in"))
      (node (ref "SENSOR") (pin "H16") (pinfunction "VDD18_H16") (pintype "power_in"))
      (node (ref "SENSOR") (pin "H22") (pinfunction "VDD18_H22") (pintype "power_in"))
      (node (ref "SENSOR") (pin "H26") (pinfunction "VDD18_H26") (pintype "power_in"))
      (node (ref "SENSOR") (pin "H5") (pinfunction "VDD18_H5") (pintype "power_in"))
      (node (ref "TP5") (pin "TP") (pinfunction "TP_TP") (pintype "input"))
      (node (ref "U5") (pin "14") (pinfunction "VCCA_14") (pintype "power_in"))
      (node (ref "U5") (pin "15") (pinfunction "DIR1_15") (pintype "input"))
      (node (ref "U5") (pin "16") (pinfunction "DIR2_16") (pintype "input"))
      (node (ref "U5") (pin "5") (pinfunction "DIR3_5") (pintype "input"))
      (node (ref "U6") (pin "14") (pinfunction "VCCA_14") (pintype "power_in"))
      (node (ref "U6") (pin "15") (pinfunction "DIR1_15") (pintype "input"))
      (node (ref "U6") (pin "5") (pinfunction "DIR3_5") (pintype "input"))
      (node (ref "U6") (pin "6") (pinfunction "DIR4_6") (pintype "input"))
      (node (ref "X-NORTH") (pin "49") (pinfunction "49_49") (pintype "bidirectional"))
      (node (ref "X-NORTH") (pin "55") (pinfunction "55_55") (pintype "bidirectional"))
      (node (ref "X-NORTH") (pin "61") (pinfunction "61_61") (pintype "bidirectional"))
      (node (ref "X-NORTH") (pin "67") (pinfunction "67_67") (pintype "bidirectional"))
      (node (ref "X-NORTH") (pin "73") (pinfunction "73_73") (pintype "bidirectional"))
      (node (ref "X-NORTH") (pin "79") (pinfunction "79_79") (pintype "bidirectional"))
      (node (ref "X-NORTH") (pin "85") (pinfunction "85_85") (pintype "bidirectional"))
      (node (ref "X-NORTH") (pin "91") (pinfunction "91_91") (pintype "bidirectional"))
      (node (ref "X-NORTH") (pin "97") (pinfunction "97_97") (pintype "bidirectional"))
    )
    (net (code "102") (name "N_VN_CV") (class "Default")
      (node (ref "C9") (pin "1") (pinfunction "1_1") (pintype "passive"))
      (node (ref "R4") (pin "1") (pinfunction "1_1") (pintype "passive"))
      (node (ref "X-NORTH") (pin "4") (pinfunction "4_4") (pintype "bidirectional"))
    )
    (net (code "103") (name "N_VN_OV") (class "Default")
      (node (ref "UNN") (pin "7") (pinfunction "OUTB_7") (pintype "output"))
      (node (ref "X-NORTH") (pin "3") (pinfunction "3_3") (pintype "bidirectional"))
    )
    (net (code "104") (name "N_VN_UV") (class "Default")
      (node (ref "UNN") (pin "1") (pinfunction "OUTA_1") (pintype "output"))
      (node (ref "X-NORTH") (pin "9") (pinfunction "9_9") (pintype "bidirectional"))
    )
    (net (code "105") (name "N_VW") (class "Default")
      (node (ref "C57") (pin "1") (pinfunction "1_1") (pintype "passive"))
      (node (ref "C58") (pin "1") (pinfunction "1_1") (pintype "passive"))
      (node (ref "C92") (pin "1") (pinfunction "1_1") (pintype "passive"))
      (node (ref "SENSOR") (pin "E2") (pinfunction "VDD_RES_E2") (pintype "power_in"))
      (node (ref "SENSOR") (pin "G4") (pinfunction "VDD_RES_G4") (pintype "power_in"))
      (node (ref "TP8") (pin "TP") (pinfunction "TP_TP") (pintype "input"))
      (node (ref "X-NORTH") (pin "13") (pinfunction "13_13") (pintype "bidirectional"))
      (node (ref "X-NORTH") (pin "19") (pinfunction "19_19") (pintype "bidirectional"))
      (node (ref "X-NORTH") (pin "25") (pinfunction "25_25") (pintype "bidirectional"))
      (node (ref "X-NORTH") (pin "31") (pinfunction "31_31") (pintype "bidirectional"))
      (node (ref "X-NORTH") (pin "37") (pinfunction "37_37") (pintype "bidirectional"))
    )
    (net (code "106") (name "N_VW_CV") (class "Default")
      (node (ref "C8") (pin "1") (pinfunction "1_1") (pintype "passive"))
      (node (ref "R1") (pin "1") (pinfunction "1_1") (pintype "passive"))
      (node (ref "X-NORTH") (pin "2") (pinfunction "2_2") (pintype "bidirectional"))
    )
    (net (code "107") (name "N_VW_OV") (class "Default")
      (node (ref "UNW") (pin "7") (pinfunction "OUTB_7") (pintype "output"))
      (node (ref "X-NORTH") (pin "1") (pinfunction "1_1") (pintype "bidirectional"))
    )
    (net (code "108") (name "N_VW_UV") (class "Default")
      (node (ref "UNW") (pin "1") (pinfunction "OUTA_1") (pintype "output"))
      (node (ref "X-NORTH") (pin "7") (pinfunction "7_7") (pintype "bidirectional"))
    )
    (net (code "109") (name "Net-(SENSORB-CMDN)") (class "Default")
      (node (ref "C61") (pin "1") (pinfunction "1_1") (pintype "passive"))
      (node (ref "SENSOR") (pin "F1") (pinfunction "CMDN_F1") (pintype "bidirectional"))
    )
    (net (code "110") (name "Net-(SENSORB-CMDP)") (class "Default")
      (node (ref "C22") (pin "2") (pinfunction "2_2") (pintype "passive"))
      (node (ref "SENSOR") (pin "F2") (pinfunction "CMDP_F2") (pintype "bidirectional"))
    )
    (net (code "111") (name "Net-(SENSORB-CMDP_COMP)") (class "Default")
      (node (ref "C28") (pin "2") (pinfunction "2_2") (pintype "passive"))
      (node (ref "SENSOR") (pin "H3") (pinfunction "CMDP_COMP_H3") (pintype "bidirectional"))
    )
    (net (code "112") (name "Net-(SENSORB-CMDP_COMP_INV)") (class "Default")
      (node (ref "C27") (pin "2") (pinfunction "2_2") (pintype "passive"))
      (node (ref "SENSOR") (pin "F3") (pinfunction "CMDP_COMP_INV_F3") (pintype "bidirectional"))
    )
    (net (code "113") (name "Net-(SENSORB-CMD_COLAMP)") (class "Default")
      (node (ref "C25") (pin "2") (pinfunction "2_2") (pintype "passive"))
      (node (ref "SENSOR") (pin "C6") (pinfunction "CMD_COLAMP_C6") (pintype "bidirectional"))
    )
    (net (code "114") (name "Net-(SENSORB-CMD_COL_LOAD)") (class "Default")
      (node (ref "C23") (pin "2") (pinfunction "2_2") (pintype "passive"))
      (node (ref "SENSOR") (pin "B1") (pinfunction "CMD_COL_LOAD_B1") (pintype "bidirectional"))
    )
    (net (code "115") (name "Net-(SENSORB-CMD_COL_PC)") (class "Default")
      (node (ref "C26") (pin "2") (pinfunction "2_2") (pintype "passive"))
      (node (ref "SENSOR") (pin "D1") (pinfunction "CMD_COL_PC_D1") (pintype "bidirectional"))
    )
    (net (code "116") (name "Net-(SENSORB-CMD_LVDS)") (class "Default")
      (node (ref "C62") (pin "1") (pinfunction "1_1") (pintype "passive"))
      (node (ref "SENSOR") (pin "C1") (pinfunction "CMD_LVDS_C1") (pintype "bidirectional"))
    )
    (net (code "117") (name "Net-(SENSORB-CMD_RAMP)") (class "Default")
      (node (ref "C24") (pin "2") (pinfunction "2_2") (pintype "passive"))
      (node (ref "SENSOR") (pin "B29") (pinfunction "CMD_RAMP_B29") (pintype "bidirectional"))
    )
    (net (code "118") (name "Net-(SENSORB-VBGAP)") (class "Default")
      (node (ref "C64") (pin "1") (pinfunction "1_1") (pintype "passive"))
      (node (ref "SENSOR") (pin "C29") (pinfunction "VBGAP_C29") (pintype "bidirectional"))
    )
    (net (code "119") (name "Net-(SENSORB-VCLAMP)") (class "Default")
      (node (ref "C63") (pin "1") (pinfunction "1_1") (pintype "passive"))
      (node (ref "SENSOR") (pin "D4") (pinfunction "VCLAMP_D4") (pintype "bidirectional"))
    )
    (net (code "120") (name "Net-(SENSORB-VCLAMP_ADC)") (class "Default")
      (node (ref "C60") (pin "1") (pinfunction "1_1") (pintype "passive"))
      (node (ref "SENSOR") (pin "G2") (pinfunction "VCLAMP_ADC_G2") (pintype "bidirectional"))
    )
    (net (code "121") (name "Net-(SENSORB-VPCH_H)") (class "Default")
      (node (ref "C71") (pin "1") (pinfunction "1_1") (pintype "passive"))
      (node (ref "SENSOR") (pin "C4") (pinfunction "VPCH_H_C4") (pintype "bidirectional"))
    )
    (net (code "122") (name "Net-(SENSORB-VPCH_L)") (class "Default")
      (node (ref "C14") (pin "1") (pinfunction "1_1") (pintype "passive"))
      (node (ref "SENSOR") (pin "A4") (pinfunction "VPCH_L_A4") (pintype "bidirectional"))
    )
    (net (code "123") (name "Net-(SENSORB-VREF)") (class "Default")
      (node (ref "C29") (pin "1") (pinfunction "1_1") (pintype "passive"))
      (node (ref "SENSOR") (pin "A3") (pinfunction "VREF_A3") (pintype "bidirectional"))
    )
    (net (code "124") (name "Net-(SENSORB-VREF_ADC)") (class "Default")
      (node (ref "C30") (pin "1") (pinfunction "1_1") (pintype "passive"))
      (node (ref "SENSOR") (pin "B3") (pinfunction "VREF_ADC_B3") (pintype "bidirectional"))
    )
    (net (code "125") (name "Net-(SENSORB-VRES_L)") (class "Default")
      (node (ref "C15") (pin "1") (pinfunction "1_1") (pintype "passive"))
      (node (ref "SENSOR") (pin "D5") (pinfunction "VRES_L_D5") (pintype "bidirectional"))
    )
    (net (code "126") (name "Net-(SENSORB-VTF_LOW0)") (class "Default")
      (node (ref "C18") (pin "1") (pinfunction "1_1") (pintype "passive"))
      (node (ref "SENSOR") (pin "C5") (pinfunction "VTF_LOW0_C5") (pintype "bidirectional"))
    )
    (net (code "127") (name "Net-(SENSORB-VTF_LOW1)") (class "Default")
      (node (ref "C19") (pin "1") (pinfunction "1_1") (pintype "passive"))
      (node (ref "SENSOR") (pin "D6") (pinfunction "VTF_LOW1_D6") (pintype "bidirectional"))
    )
    (net (code "128") (name "Net-(SENSORB-VTF_LOW2)") (class "Default")
      (node (ref "C20") (pin "1") (pinfunction "1_1") (pintype "passive"))
      (node (ref "SENSOR") (pin "B30") (pinfunction "VTF_LOW2_B30") (pintype "bidirectional"))
    )
    (net (code "129") (name "Net-(SENSORB-VTF_LOW3)") (class "Default")
      (node (ref "C21") (pin "1") (pinfunction "1_1") (pintype "passive"))
      (node (ref "SENSOR") (pin "C30") (pinfunction "VTF_LOW3_C30") (pintype "bidirectional"))
    )
    (net (code "130") (name "Net-(U3-ADJ)") (class "Default")
      (node (ref "R21") (pin "1") (pinfunction "1_1") (pintype "passive"))
      (node (ref "R22") (pin "2") (pinfunction "2_2") (pintype "passive"))
      (node (ref "U3") (pin "5") (pinfunction "ADJ_5") (pintype "input"))
    )
    (net (code "131") (name "Net-(U6-B4)") (class "Default")
      (node (ref "TP9") (pin "TP") (pinfunction "TP_TP") (pintype "input"))
      (node (ref "U6") (pin "9") (pinfunction "B4_9") (pintype "bidirectional"))
    )
    (net (code "132") (name "Net-(UEP-WP)") (class "Default")
      (node (ref "R1X") (pin "2") (pinfunction "2_2") (pintype "passive"))
      (node (ref "R2X") (pin "1") (pinfunction "1_1") (pintype "passive"))
      (node (ref "UEP") (pin "7") (pinfunction "WP_7") (pintype "input"))
    )
    (net (code "133") (name "Net-(UNE-VINA+)") (class "Default")
      (node (ref "R7") (pin "2") (pinfunction "2_2") (pintype "passive"))
      (node (ref "R8") (pin "1") (pinfunction "1_1") (pintype "passive"))
      (node (ref "UNE") (pin "3") (pinfunction "VINA+_3") (pintype "input"))
    )
    (net (code "134") (name "Net-(UNE-VINB-)") (class "Default")
      (node (ref "R8") (pin "2") (pinfunction "2_2") (pintype "passive"))
      (node (ref "R9") (pin "1") (pinfunction "1_1") (pintype "passive"))
      (node (ref "UNE") (pin "6") (pinfunction "VINB-_6") (pintype "input"))
    )
    (net (code "135") (name "Net-(UNN-VINA+)") (class "Default")
      (node (ref "R4") (pin "2") (pinfunction "2_2") (pintype "passive"))
      (node (ref "R5") (pin "1") (pinfunction "1_1") (pintype "passive"))
      (node (ref "UNN") (pin "3") (pinfunction "VINA+_3") (pintype "input"))
    )
    (net (code "136") (name "Net-(UNN-VINB-)") (class "Default")
      (node (ref "R5") (pin "2") (pinfunction "2_2") (pintype "passive"))
      (node (ref "R6") (pin "1") (pinfunction "1_1") (pintype "passive"))
      (node (ref "UNN") (pin "6") (pinfunction "VINB-_6") (pintype "input"))
    )
    (net (code "137") (name "Net-(UNW-VINA+)") (class "Default")
      (node (ref "R1") (pin "2") (pinfunction "2_2") (pintype "passive"))
      (node (ref "R2") (pin "1") (pinfunction "1_1") (pintype "passive"))
      (node (ref "UNW") (pin "3") (pinfunction "VINA+_3") (pintype "input"))
    )
    (net (code "138") (name "Net-(UNW-VINB-)") (class "Default")
      (node (ref "R2") (pin "2") (pinfunction "2_2") (pintype "passive"))
      (node (ref "R3") (pin "1") (pinfunction "1_1") (pintype "passive"))
      (node (ref "UNW") (pin "6") (pinfunction "VINB-_6") (pintype "input"))
    )
    (net (code "139") (name "Net-(USE-VINA+)") (class "Default")
      (node (ref "R10") (pin "2") (pinfunction "2_2") (pintype "passive"))
      (node (ref "R11") (pin "1") (pinfunction "1_1") (pintype "passive"))
      (node (ref "USE") (pin "3") (pinfunction "VINA+_3") (pintype "input"))
    )
    (net (code "140") (name "Net-(USE-VINB-)") (class "Default")
      (node (ref "R11") (pin "2") (pinfunction "2_2") (pintype "passive"))
      (node (ref "R12") (pin "1") (pinfunction "1_1") (pintype "passive"))
      (node (ref "USE") (pin "6") (pinfunction "VINB-_6") (pintype "input"))
    )
    (net (code "141") (name "Net-(USS-VINA+)") (class "Default")
      (node (ref "R13") (pin "2") (pinfunction "2_2") (pintype "passive"))
      (node (ref "R14") (pin "1") (pinfunction "1_1") (pintype "passive"))
      (node (ref "USS") (pin "3") (pinfunction "VINA+_3") (pintype "input"))
    )
    (net (code "142") (name "Net-(USS-VINB-)") (class "Default")
      (node (ref "R14") (pin "2") (pinfunction "2_2") (pintype "passive"))
      (node (ref "R15") (pin "1") (pinfunction "1_1") (pintype "passive"))
      (node (ref "USS") (pin "6") (pinfunction "VINB-_6") (pintype "input"))
    )
    (net (code "143") (name "Net-(USW-VINA+)") (class "Default")
      (node (ref "R16") (pin "2") (pinfunction "2_2") (pintype "passive"))
      (node (ref "R17") (pin "1") (pinfunction "1_1") (pintype "passive"))
      (node (ref "USW") (pin "3") (pinfunction "VINA+_3") (pintype "input"))
    )
    (net (code "144") (name "Net-(USW-VINB-)") (class "Default")
      (node (ref "R17") (pin "2") (pinfunction "2_2") (pintype "passive"))
      (node (ref "R18") (pin "1") (pinfunction "1_1") (pintype "passive"))
      (node (ref "USW") (pin "6") (pinfunction "VINB-_6") (pintype "input"))
    )
    (net (code "145") (name "S00_N") (class "Default")
      (node (ref "X-SOUTH") (pin "16") (pinfunction "16_16") (pintype "bidirectional"))
    )
    (net (code "146") (name "S00_P") (class "Default")
      (node (ref "X-SOUTH") (pin "14") (pinfunction "14_14") (pintype "bidirectional"))
    )
    (net (code "147") (name "S01_N") (class "Default")
      (node (ref "X-SOUTH") (pin "17") (pinfunction "17_17") (pintype "bidirectional"))
    )
    (net (code "148") (name "S01_P") (class "Default")
      (node (ref "X-SOUTH") (pin "15") (pinfunction "15_15") (pintype "bidirectional"))
    )
    (net (code "149") (name "S02_N") (class "Default")
      (node (ref "X-SOUTH") (pin "22") (pinfunction "22_22") (pintype "bidirectional"))
    )
    (net (code "150") (name "S02_P") (class "Default")
      (node (ref "X-SOUTH") (pin "20") (pinfunction "20_20") (pintype "bidirectional"))
    )
    (net (code "151") (name "S03_N") (class "Default")
      (node (ref "X-SOUTH") (pin "23") (pinfunction "23_23") (pintype "bidirectional"))
    )
    (net (code "152") (name "S03_P") (class "Default")
      (node (ref "X-SOUTH") (pin "21") (pinfunction "21_21") (pintype "bidirectional"))
    )
    (net (code "153") (name "S04_N") (class "Default")
      (node (ref "SENSOR") (pin "C24") (pinfunction "OUT32_N_C24") (pintype "output"))
      (node (ref "X-SOUTH") (pin "28") (pinfunction "28_28") (pintype "bidirectional"))
    )
    (net (code "154") (name "S04_P") (class "Default")
      (node (ref "SENSOR") (pin "C25") (pinfunction "OUT32_P_C25") (pintype "output"))
      (node (ref "X-SOUTH") (pin "26") (pinfunction "26_26") (pintype "bidirectional"))
    )
    (net (code "155") (name "S05_N") (class "Default")
      (node (ref "X-SOUTH") (pin "29") (pinfunction "29_29") (pintype "bidirectional"))
    )
    (net (code "156") (name "S05_P") (class "Default")
      (node (ref "X-SOUTH") (pin "27") (pinfunction "27_27") (pintype "bidirectional"))
    )
    (net (code "157") (name "S06_N") (class "Default")
      (node (ref "SENSOR") (pin "D23") (pinfunction "OUT30_N_D23") (pintype "output"))
      (node (ref "X-SOUTH") (pin "34") (pinfunction "34_34") (pintype "bidirectional"))
    )
    (net (code "158") (name "S06_P") (class "Default")
      (node (ref "SENSOR") (pin "D24") (pinfunction "OUT30_P_D24") (pintype "output"))
      (node (ref "X-SOUTH") (pin "32") (pinfunction "32_32") (pintype "bidirectional"))
    )
    (net (code "159") (name "S07_N") (class "Default")
      (node (ref "SENSOR") (pin "B24") (pinfunction "OUT31_N_B24") (pintype "output"))
      (node (ref "X-SOUTH") (pin "35") (pinfunction "35_35") (pintype "bidirectional"))
    )
    (net (code "160") (name "S07_P") (class "Default")
      (node (ref "SENSOR") (pin "B25") (pinfunction "OUT31_P_B25") (pintype "output"))
      (node (ref "X-SOUTH") (pin "33") (pinfunction "33_33") (pintype "bidirectional"))
    )
    (net (code "161") (name "S08_N") (class "Default")
      (node (ref "SENSOR") (pin "D21") (pinfunction "OUT27_N_D21") (pintype "output"))
      (node (ref "X-SOUTH") (pin "40") (pinfunction "40_40") (pintype "bidirectional"))
    )
    (net (code "162") (name "S08_P") (class "Default")
      (node (ref "SENSOR") (pin "D22") (pinfunction "OUT27_P_D22") (pintype "output"))
      (node (ref "X-SOUTH") (pin "38") (pinfunction "38_38") (pintype "bidirectional"))
    )
    (net (code "163") (name "S09_N") (class "Default")
      (node (ref "SENSOR") (pin "A23") (pinfunction "OUT29_N_A23") (pintype "output"))
      (node (ref "X-SOUTH") (pin "41") (pinfunction "41_41") (pintype "bidirectional"))
    )
    (net (code "164") (name "S09_P") (class "Default")
      (node (ref "SENSOR") (pin "A24") (pinfunction "OUT29_P_A24") (pintype "output"))
      (node (ref "X-SOUTH") (pin "39") (pinfunction "39_39") (pintype "bidirectional"))
    )
    (net (code "165") (name "S10_N") (class "Default")
      (node (ref "SENSOR") (pin "C21") (pinfunction "OUT28_N_C21") (pintype "output"))
      (node (ref "X-SOUTH") (pin "46") (pinfunction "46_46") (pintype "bidirectional"))
    )
    (net (code "166") (name "S10_P") (class "Default")
      (node (ref "SENSOR") (pin "C22") (pinfunction "OUT28_P_C22") (pintype "output"))
      (node (ref "X-SOUTH") (pin "44") (pinfunction "44_44") (pintype "bidirectional"))
    )
    (net (code "167") (name "S11_N") (class "Default")
      (node (ref "SENSOR") (pin "B20") (pinfunction "OUT26_N_B20") (pintype "output"))
      (node (ref "X-SOUTH") (pin "47") (pinfunction "47_47") (pintype "bidirectional"))
    )
    (net (code "168") (name "S11_P") (class "Default")
      (node (ref "SENSOR") (pin "B21") (pinfunction "OUT26_P_B21") (pintype "output"))
      (node (ref "X-SOUTH") (pin "45") (pinfunction "45_45") (pintype "bidirectional"))
    )
    (net (code "169") (name "S12_N") (class "Default")
      (node (ref "SENSOR") (pin "D19") (pinfunction "OUT24_N_D19") (pintype "output"))
      (node (ref "X-SOUTH") (pin "52") (pinfunction "52_52") (pintype "bidirectional"))
    )
    (net (code "170") (name "S12_P") (class "Default")
      (node (ref "SENSOR") (pin "D20") (pinfunction "OUT24_P_D20") (pintype "output"))
      (node (ref "X-SOUTH") (pin "50") (pinfunction "50_50") (pintype "bidirectional"))
    )
    (net (code "171") (name "S13_N") (class "Default")
      (node (ref "SENSOR") (pin "A19") (pinfunction "OUT23_N_A19") (pintype "output"))
      (node (ref "X-SOUTH") (pin "53") (pinfunction "53_53") (pintype "bidirectional"))
    )
    (net (code "172") (name "S13_P") (class "Default")
      (node (ref "SENSOR") (pin "A20") (pinfunction "OUT23_P_A20") (pintype "output"))
      (node (ref "X-SOUTH") (pin "51") (pinfunction "51_51") (pintype "bidirectional"))
    )
    (net (code "173") (name "S14_N") (class "Default")
      (node (ref "SENSOR") (pin "C19") (pinfunction "OUT25_N_C19") (pintype "output"))
      (node (ref "X-SOUTH") (pin "58") (pinfunction "58_58") (pintype "bidirectional"))
    )
    (net (code "174") (name "S14_P") (class "Default")
      (node (ref "SENSOR") (pin "C20") (pinfunction "OUT25_P_C20") (pintype "output"))
      (node (ref "X-SOUTH") (pin "56") (pinfunction "56_56") (pintype "bidirectional"))
    )
    (net (code "175") (name "S15_N") (class "Default")
      (node (ref "SENSOR") (pin "B18") (pinfunction "OUT22_N_B18") (pintype "output"))
      (node (ref "X-SOUTH") (pin "59") (pinfunction "59_59") (pintype "bidirectional"))
    )
    (net (code "176") (name "S15_P") (class "Default")
      (node (ref "SENSOR") (pin "B19") (pinfunction "OUT22_P_B19") (pintype "output"))
      (node (ref "X-SOUTH") (pin "57") (pinfunction "57_57") (pintype "bidirectional"))
    )
    (net (code "177") (name "S16_N") (class "Default")
      (node (ref "SENSOR") (pin "C17") (pinfunction "OUT21_N_C17") (pintype "output"))
      (node (ref "X-SOUTH") (pin "64") (pinfunction "64_64") (pintype "bidirectional"))
    )
    (net (code "178") (name "S16_P") (class "Default")
      (node (ref "SENSOR") (pin "C18") (pinfunction "OUT21_P_C18") (pintype "output"))
      (node (ref "X-SOUTH") (pin "62") (pinfunction "62_62") (pintype "bidirectional"))
    )
    (net (code "179") (name "S17_N") (class "Default")
      (node (ref "SENSOR") (pin "A17") (pinfunction "OUT19_N_A17") (pintype "output"))
      (node (ref "X-SOUTH") (pin "65") (pinfunction "65_65") (pintype "bidirectional"))
    )
    (net (code "180") (name "S17_P") (class "Default")
      (node (ref "SENSOR") (pin "A18") (pinfunction "OUT19_P_A18") (pintype "output"))
      (node (ref "X-SOUTH") (pin "63") (pinfunction "63_63") (pintype "bidirectional"))
    )
    (net (code "181") (name "S18_N") (class "Default")
      (node (ref "SENSOR") (pin "D17") (pinfunction "OUT20_N_D17") (pintype "output"))
      (node (ref "X-SOUTH") (pin "70") (pinfunction "70_70") (pintype "bidirectional"))
    )
    (net (code "182") (name "S18_P") (class "Default")
      (node (ref "SENSOR") (pin "D18") (pinfunction "OUT20_P_D18") (pintype "output"))
      (node (ref "X-SOUTH") (pin "68") (pinfunction "68_68") (pintype "bidirectional"))
    )
    (net (code "183") (name "S19_N") (class "Default")
      (node (ref "SENSOR") (pin "B16") (pinfunction "OUT18_N_B16") (pintype "output"))
      (node (ref "X-SOUTH") (pin "71") (pinfunction "71_71") (pintype "bidirectional"))
    )
    (net (code "184") (name "S19_P") (class "Default")
      (node (ref "SENSOR") (pin "B17") (pinfunction "OUT18_P_B17") (pintype "output"))
      (node (ref "X-SOUTH") (pin "69") (pinfunction "69_69") (pintype "bidirectional"))
    )
    (net (code "185") (name "S20_N") (class "Default")
      (node (ref "SENSOR") (pin "D15") (pinfunction "OUT17_N_D15") (pintype "output"))
      (node (ref "X-SOUTH") (pin "76") (pinfunction "76_76") (pintype "bidirectional"))
    )
    (net (code "186") (name "S20_P") (class "Default")
      (node (ref "SENSOR") (pin "D16") (pinfunction "OUT17_P_D16") (pintype "output"))
      (node (ref "X-SOUTH") (pin "74") (pinfunction "74_74") (pintype "bidirectional"))
    )
    (net (code "187") (name "S21_N") (class "Default")
      (node (ref "SENSOR") (pin "B14") (pinfunction "OUT16_N_B14") (pintype "output"))
      (node (ref "X-SOUTH") (pin "77") (pinfunction "77_77") (pintype "bidirectional"))
    )
    (net (code "188") (name "S21_P") (class "Default")
      (node (ref "SENSOR") (pin "B15") (pinfunction "OUT16_P_B15") (pintype "output"))
      (node (ref "X-SOUTH") (pin "75") (pinfunction "75_75") (pintype "bidirectional"))
    )
    (net (code "189") (name "S22_N") (class "Default")
      (node (ref "SENSOR") (pin "D13") (pinfunction "OUT15_N_D13") (pintype "output"))
      (node (ref "X-SOUTH") (pin "82") (pinfunction "82_82") (pintype "bidirectional"))
    )
    (net (code "190") (name "S22_P") (class "Default")
      (node (ref "SENSOR") (pin "D14") (pinfunction "OUT15_P_D14") (pintype "output"))
      (node (ref "X-SOUTH") (pin "80") (pinfunction "80_80") (pintype "bidirectional"))
    )
    (net (code "191") (name "S23_N") (class "Default")
      (node (ref "SENSOR") (pin "A13") (pinfunction "OUT13_N_A13") (pintype "output"))
      (node (ref "X-SOUTH") (pin "83") (pinfunction "83_83") (pintype "bidirectional"))
    )
    (net (code "192") (name "S23_P") (class "Default")
      (node (ref "SENSOR") (pin "A14") (pinfunction "OUT13_P_A14") (pintype "output"))
      (node (ref "X-SOUTH") (pin "81") (pinfunction "81_81") (pintype "bidirectional"))
    )
    (net (code "193") (name "S24_N") (class "Default")
      (node (ref "SENSOR") (pin "C13") (pinfunction "OUT14_N_C13") (pintype "output"))
      (node (ref "X-SOUTH") (pin "88") (pinfunction "88_88") (pintype "bidirectional"))
    )
    (net (code "194") (name "S24_P") (class "Default")
      (node (ref "SENSOR") (pin "C14") (pinfunction "OUT14_P_C14") (pintype "output"))
      (node (ref "X-SOUTH") (pin "86") (pinfunction "86_86") (pintype "bidirectional"))
    )
    (net (code "195") (name "S25_N") (class "Default")
      (node (ref "SENSOR") (pin "B12") (pinfunction "OUT12_N_B12") (pintype "output"))
      (node (ref "X-SOUTH") (pin "89") (pinfunction "89_89") (pintype "bidirectional"))
    )
    (net (code "196") (name "S25_P") (class "Default")
      (node (ref "SENSOR") (pin "B13") (pinfunction "OUT12_P_B13") (pintype "output"))
      (node (ref "X-SOUTH") (pin "87") (pinfunction "87_87") (pintype "bidirectional"))
    )
    (net (code "197") (name "S26_N") (class "Default")
      (node (ref "SENSOR") (pin "D11") (pinfunction "OUT10_N_D11") (pintype "output"))
      (node (ref "X-SOUTH") (pin "94") (pinfunction "94_94") (pintype "bidirectional"))
    )
    (net (code "198") (name "S26_P") (class "Default")
      (node (ref "SENSOR") (pin "D12") (pinfunction "OUT10_P_D12") (pintype "output"))
      (node (ref "X-SOUTH") (pin "92") (pinfunction "92_92") (pintype "bidirectional"))
    )
    (net (code "199") (name "S27_N") (class "Default")
      (node (ref "SENSOR") (pin "A11") (pinfunction "OUT9_N_A11") (pintype "output"))
      (node (ref "X-SOUTH") (pin "95") (pinfunction "95_95") (pintype "bidirectional"))
    )
    (net (code "200") (name "S27_P") (class "Default")
      (node (ref "SENSOR") (pin "A12") (pinfunction "OUT9_P_A12") (pintype "output"))
      (node (ref "X-SOUTH") (pin "93") (pinfunction "93_93") (pintype "bidirectional"))
    )
    (net (code "201") (name "S28_N") (class "Default")
      (node (ref "SENSOR") (pin "C11") (pinfunction "OUT11_N_C11") (pintype "output"))
      (node (ref "X-SOUTH") (pin "100") (pinfunction "100_100") (pintype "bidirectional"))
    )
    (net (code "202") (name "S28_P") (class "Default")
      (node (ref "SENSOR") (pin "C12") (pinfunction "OUT11_P_C12") (pintype "output"))
      (node (ref "X-SOUTH") (pin "98") (pinfunction "98_98") (pintype "bidirectional"))
    )
    (net (code "203") (name "S29_N") (class "Default")
      (node (ref "SENSOR") (pin "B10") (pinfunction "OUT8_N_B10") (pintype "output"))
      (node (ref "X-SOUTH") (pin "101") (pinfunction "101_101") (pintype "bidirectional"))
    )
    (net (code "204") (name "S29_P") (class "Default")
      (node (ref "SENSOR") (pin "B11") (pinfunction "OUT8_P_B11") (pintype "output"))
      (node (ref "X-SOUTH") (pin "99") (pinfunction "99_99") (pintype "bidirectional"))
    )
    (net (code "205") (name "S30_N") (class "Default")
      (node (ref "SENSOR") (pin "C9") (pinfunction "OUT7_N_C9") (pintype "output"))
      (node (ref "X-SOUTH") (pin "106") (pinfunction "106_106") (pintype "bidirectional"))
    )
    (net (code "206") (name "S30_P") (class "Default")
      (node (ref "SENSOR") (pin "C10") (pinfunction "OUT7_P_C10") (pintype "output"))
      (node (ref "X-SOUTH") (pin "104") (pinfunction "104_104") (pintype "bidirectional"))
    )
    (net (code "207") (name "S31_N") (class "Default")
      (node (ref "SENSOR") (pin "B8") (pinfunction "OUT5_N_B8") (pintype "output"))
      (node (ref "X-SOUTH") (pin "107") (pinfunction "107_107") (pintype "bidirectional"))
    )
    (net (code "208") (name "S31_P") (class "Default")
      (node (ref "SENSOR") (pin "B9") (pinfunction "OUT5_P_B9") (pintype "output"))
      (node (ref "X-SOUTH") (pin "105") (pinfunction "105_105") (pintype "bidirectional"))
    )
    (net (code "209") (name "S32_N") (class "Default")
      (node (ref "SENSOR") (pin "D9") (pinfunction "OUT6_N_D9") (pintype "output"))
      (node (ref "X-SOUTH") (pin "112") (pinfunction "112_112") (pintype "bidirectional"))
    )
    (net (code "210") (name "S32_P") (class "Default")
      (node (ref "SENSOR") (pin "D10") (pinfunction "OUT6_P_D10") (pintype "output"))
      (node (ref "X-SOUTH") (pin "110") (pinfunction "110_110") (pintype "bidirectional"))
    )
    (net (code "211") (name "S33_N") (class "Default")
      (node (ref "SENSOR") (pin "A7") (pinfunction "OUT2_N_A7") (pintype "output"))
      (node (ref "X-SOUTH") (pin "113") (pinfunction "113_113") (pintype "bidirectional"))
    )
    (net (code "212") (name "S33_P") (class "Default")
      (node (ref "SENSOR") (pin "A8") (pinfunction "OUT2_P_A8") (pintype "output"))
      (node (ref "X-SOUTH") (pin "111") (pinfunction "111_111") (pintype "bidirectional"))
    )
    (net (code "213") (name "S34_N") (class "Default")
      (node (ref "SENSOR") (pin "C7") (pinfunction "OUT4_N_C7") (pintype "output"))
      (node (ref "X-SOUTH") (pin "118") (pinfunction "118_118") (pintype "bidirectional"))
    )
    (net (code "214") (name "S34_P") (class "Default")
      (node (ref "SENSOR") (pin "C8") (pinfunction "OUT4_P_C8") (pintype "output"))
      (node (ref "X-SOUTH") (pin "116") (pinfunction "116_116") (pintype "bidirectional"))
    )
    (net (code "215") (name "S35_N") (class "Default")
      (node (ref "SENSOR") (pin "B6") (pinfunction "OUT1_N_B6") (pintype "output"))
      (node (ref "X-SOUTH") (pin "119") (pinfunction "119_119") (pintype "bidirectional"))
    )
    (net (code "216") (name "S35_P") (class "Default")
      (node (ref "SENSOR") (pin "B7") (pinfunction "OUT1_P_B7") (pintype "output"))
      (node (ref "X-SOUTH") (pin "117") (pinfunction "117_117") (pintype "bidirectional"))
    )
    (net (code "217") (name "S36_N") (class "Default")
      (node (ref "SENSOR") (pin "D7") (pinfunction "OUT3_N_D7") (pintype "output"))
      (node (ref "X-SOUTH") (pin "124") (pinfunction "124_124") (pintype "bidirectional"))
    )
    (net (code "218") (name "S36_P") (class "Default")
      (node (ref "SENSOR") (pin "D8") (pinfunction "OUT3_P_D8") (pintype "output"))
      (node (ref "X-SOUTH") (pin "122") (pinfunction "122_122") (pintype "bidirectional"))
    )
    (net (code "219") (name "S37_N") (class "Default")
      (node (ref "SENSOR") (pin "A5") (pinfunction "OUTCTR_N_A5") (pintype "output"))
      (node (ref "X-SOUTH") (pin "125") (pinfunction "125_125") (pintype "bidirectional"))
    )
    (net (code "220") (name "S37_P") (class "Default")
      (node (ref "SENSOR") (pin "A6") (pinfunction "OUTCTR_P_A6") (pintype "output"))
      (node (ref "X-SOUTH") (pin "123") (pinfunction "123_123") (pintype "bidirectional"))
    )
    (net (code "221") (name "S38_N") (class "Default")
      (node (ref "X-SOUTH") (pin "130") (pinfunction "130_130") (pintype "bidirectional"))
    )
    (net (code "222") (name "S38_P") (class "Default")
      (node (ref "X-SOUTH") (pin "128") (pinfunction "128_128") (pintype "bidirectional"))
    )
    (net (code "223") (name "S39_N") (class "Default")
      (node (ref "U3") (pin "6") (pinfunction "EN_6") (pintype "input"))
      (node (ref "X-SOUTH") (pin "131") (pinfunction "131_131") (pintype "bidirectional"))
    )
    (net (code "224") (name "S39_P") (class "Default")
      (node (ref "X-SOUTH") (pin "129") (pinfunction "129_129") (pintype "bidirectional"))
    )
    (net (code "225") (name "SPI_CLK") (class "Default")
      (node (ref "SENSOR") (pin "H29") (pinfunction "SPI_CLK_H29") (pintype "input"))
      (node (ref "U4") (pin "9") (pinfunction "B4_9") (pintype "bidirectional"))
    )
    (net (code "226") (name "SPI_EN") (class "Default")
      (node (ref "SENSOR") (pin "F28") (pinfunction "SPI_EN_F28") (pintype "input"))
      (node (ref "U4") (pin "12") (pinfunction "B1_12") (pintype "bidirectional"))
    )
    (net (code "227") (name "SPI_IN") (class "Default")
      (node (ref "SENSOR") (pin "E28") (pinfunction "SPI_IN_E28") (pintype "input"))
      (node (ref "U4") (pin "10") (pinfunction "B3_10") (pintype "bidirectional"))
    )
    (net (code "228") (name "SPI_OUT") (class "Default")
      (node (ref "SENSOR") (pin "G28") (pinfunction "SPI_OUT_G28") (pintype "output"))
      (node (ref "U4") (pin "11") (pinfunction "B2_11") (pintype "bidirectional"))
    )
    (net (code "229") (name "SYS_RES_N") (class "Default")
      (node (ref "SENSOR") (pin "F30") (pinfunction "SYS_RES_N_F30") (pintype "input"))
      (node (ref "U5") (pin "10") (pinfunction "B3_10") (pintype "bidirectional"))
    )
    (net (code "230") (name "S_CHK_EN") (class "Default")
      (node (ref "X-SOUTH") (pin "8") (pinfunction "8_8") (pintype "bidirectional"))
    )
    (net (code "231") (name "S_CHK_V") (class "Default")
      (node (ref "C5") (pin "1") (pinfunction "1_1") (pintype "passive"))
      (node (ref "C6") (pin "1") (pinfunction "1_1") (pintype "passive"))
      (node (ref "C7") (pin "1") (pinfunction "1_1") (pintype "passive"))
      (node (ref "R20") (pin "1") (pinfunction "1_1") (pintype "passive"))
      (node (ref "TP3") (pin "TP") (pinfunction "TP_TP") (pintype "input"))
      (node (ref "USE") (pin "8") (pinfunction "VDD_8") (pintype "power_in"))
      (node (ref "USS") (pin "8") (pinfunction "VDD_8") (pintype "power_in"))
      (node (ref "USW") (pin "8") (pinfunction "VDD_8") (pintype "power_in"))
      (node (ref "X-SOUTH") (pin "10") (pinfunction "10_10") (pintype "bidirectional"))
    )
    (net (code "232") (name "S_I2C_EN") (class "Default")
      (node (ref "X-SOUTH") (pin "137") (pinfunction "137_137") (pintype "bidirectional"))
    )
    (net (code "233") (name "S_I2C_V") (class "Default")
      (node (ref "U7") (pin "8") (pinfunction "VCC_8") (pintype "power_in"))
      (node (ref "X-SOUTH") (pin "135") (pinfunction "135_135") (pintype "bidirectional"))
    )
    (net (code "234") (name "S_REF") (class "Default")
      (node (ref "R20") (pin "2") (pinfunction "2_2") (pintype "passive"))
      (node (ref "TP4") (pin "TP") (pinfunction "TP_TP") (pintype "input"))
      (node (ref "U2") (pin "1") (pinfunction "CATHODE_1") (pintype "output"))
      (node (ref "U2") (pin "3") (pinfunction "REF_3") (pintype "input"))
      (node (ref "USE") (pin "2") (pinfunction "VINA-_2") (pintype "input"))
      (node (ref "USE") (pin "5") (pinfunction "VINB+_5") (pintype "input"))
      (node (ref "USS") (pin "2") (pinfunction "VINA-_2") (pintype "input"))
      (node (ref "USS") (pin "5") (pinfunction "VINB+_5") (pintype "input"))
      (node (ref "USW") (pin "2") (pinfunction "VINA-_2") (pintype "input"))
      (node (ref "USW") (pin "5") (pinfunction "VINB+_5") (pintype "input"))
    )
    (net (code "235") (name "S_SCK") (class "Default")
      (node (ref "X-SOUTH") (pin "144") (pinfunction "144_144") (pintype "bidirectional"))
    )
    (net (code "236") (name "S_SCL") (class "Default")
      (node (ref "U7") (pin "2") (pinfunction "SCL_2") (pintype "input"))
      (node (ref "X-SOUTH") (pin "143") (pinfunction "143_143") (pintype "bidirectional"))
    )
    (net (code "237") (name "S_SDA") (class "Default")
      (node (ref "U7") (pin "1") (pinfunction "SDA_1") (pintype "bidirectional"))
      (node (ref "X-SOUTH") (pin "141") (pinfunction "141_141") (pintype "bidirectional"))
    )
    (net (code "238") (name "S_SDI") (class "Default")
      (node (ref "X-SOUTH") (pin "140") (pinfunction "140_140") (pintype "bidirectional"))
    )
    (net (code "239") (name "S_SDO") (class "Default")
      (node (ref "X-SOUTH") (pin "142") (pinfunction "142_142") (pintype "bidirectional"))
    )
    (net (code "240") (name "S_SPI_EN") (class "Default")
      (node (ref "X-SOUTH") (pin "136") (pinfunction "136_136") (pintype "bidirectional"))
    )
    (net (code "241") (name "S_SPI_V") (class "Default")
      (node (ref "X-SOUTH") (pin "134") (pinfunction "134_134") (pintype "bidirectional"))
    )
    (net (code "242") (name "S_VE") (class "Default")
      (node (ref "X-SOUTH") (pin "13") (pinfunction "13_13") (pintype "bidirectional"))
      (node (ref "X-SOUTH") (pin "19") (pinfunction "19_19") (pintype "bidirectional"))
      (node (ref "X-SOUTH") (pin "25") (pinfunction "25_25") (pintype "bidirectional"))
      (node (ref "X-SOUTH") (pin "31") (pinfunction "31_31") (pintype "bidirectional"))
      (node (ref "X-SOUTH") (pin "37") (pinfunction "37_37") (pintype "bidirectional"))
    )
    (net (code "243") (name "S_VE_CV") (class "Default")
      (node (ref "C11") (pin "1") (pinfunction "1_1") (pintype "passive"))
      (node (ref "R10") (pin "1") (pinfunction "1_1") (pintype "passive"))
      (node (ref "X-SOUTH") (pin "2") (pinfunction "2_2") (pintype "bidirectional"))
    )
    (net (code "244") (name "S_VE_OV") (class "Default")
      (node (ref "USE") (pin "7") (pinfunction "OUTB_7") (pintype "output"))
      (node (ref "X-SOUTH") (pin "1") (pinfunction "1_1") (pintype "bidirectional"))
    )
    (net (code "245") (name "S_VE_UV") (class "Default")
      (node (ref "USE") (pin "1") (pinfunction "OUTA_1") (pintype "output"))
      (node (ref "X-SOUTH") (pin "7") (pinfunction "7_7") (pintype "bidirectional"))
    )
    (net (code "246") (name "S_VS") (class "Default")
      (node (ref "C45") (pin "1") (pinfunction "1_1") (pintype "passive"))
      (node (ref "C46") (pin "1") (pinfunction "1_1") (pintype "passive"))
      (node (ref "C47") (pin "1") (pinfunction "1_1") (pintype "passive"))
      (node (ref "C48") (pin "1") (pinfunction "1_1") (pintype "passive"))
      (node (ref "C49") (pin "1") (pinfunction "1_1") (pintype "passive"))
      (node (ref "C72") (pin "1") (pinfunction "1_1") (pintype "passive"))
      (node (ref "C73") (pin "1") (pinfunction "1_1") (pintype "passive"))
      (node (ref "C74") (pin "1") (pinfunction "1_1") (pintype "passive"))
      (node (ref "C81") (pin "1") (pinfunction "1_1") (pintype "passive"))
      (node (ref "C82") (pin "1") (pinfunction "1_1") (pintype "passive"))
      (node (ref "C83") (pin "1") (pinfunction "1_1") (pintype "passive"))
      (node (ref "SENSOR") (pin "A30") (pinfunction "VDD_PIX_A30") (pintype "power_in"))
      (node (ref "SENSOR") (pin "D28") (pinfunction "VDD_PIX_D28") (pintype "power_in"))
      (node (ref "SENSOR") (pin "D30") (pinfunction "VDD_PIX_D30") (pintype "power_in"))
      (node (ref "SENSOR") (pin "G1") (pinfunction "VDD_PIX_G1") (pintype "power_in"))
      (node (ref "SENSOR") (pin "H28") (pinfunction "VDD_PIX_H28") (pintype "power_in"))
      (node (ref "TP6") (pin "TP") (pinfunction "TP_TP") (pintype "input"))
      (node (ref "X-SOUTH") (pin "49") (pinfunction "49_49") (pintype "bidirectional"))
      (node (ref "X-SOUTH") (pin "55") (pinfunction "55_55") (pintype "bidirectional"))
      (node (ref "X-SOUTH") (pin "61") (pinfunction "61_61") (pintype "bidirectional"))
      (node (ref "X-SOUTH") (pin "67") (pinfunction "67_67") (pintype "bidirectional"))
      (node (ref "X-SOUTH") (pin "73") (pinfunction "73_73") (pintype "bidirectional"))
      (node (ref "X-SOUTH") (pin "79") (pinfunction "79_79") (pintype "bidirectional"))
      (node (ref "X-SOUTH") (pin "85") (pinfunction "85_85") (pintype "bidirectional"))
      (node (ref "X-SOUTH") (pin "91") (pinfunction "91_91") (pintype "bidirectional"))
      (node (ref "X-SOUTH") (pin "97") (pinfunction "97_97") (pintype "bidirectional"))
    )
    (net (code "247") (name "S_VS_CV") (class "Default")
      (node (ref "C12") (pin "1") (pinfunction "1_1") (pintype "passive"))
      (node (ref "R13") (pin "1") (pinfunction "1_1") (pintype "passive"))
      (node (ref "X-SOUTH") (pin "4") (pinfunction "4_4") (pintype "bidirectional"))
    )
    (net (code "248") (name "S_VS_OV") (class "Default")
      (node (ref "USS") (pin "7") (pinfunction "OUTB_7") (pintype "output"))
      (node (ref "X-SOUTH") (pin "3") (pinfunction "3_3") (pintype "bidirectional"))
    )
    (net (code "249") (name "S_VS_UV") (class "Default")
      (node (ref "USS") (pin "1") (pinfunction "OUTA_1") (pintype "output"))
      (node (ref "X-SOUTH") (pin "9") (pinfunction "9_9") (pintype "bidirectional"))
    )
    (net (code "250") (name "S_VW") (class "Default")
      (node (ref "C90") (pin "1") (pinfunction "1_1") (pintype "passive"))
      (node (ref "U3") (pin "1") (pinfunction "BIAS_1") (pintype "power_in"))
      (node (ref "U3") (pin "3") (pinfunction "IN_3") (pintype "power_in"))
      (node (ref "X-SOUTH") (pin "109") (pinfunction "109_109") (pintype "bidirectional"))
      (node (ref "X-SOUTH") (pin "115") (pinfunction "115_115") (pintype "bidirectional"))
      (node (ref "X-SOUTH") (pin "121") (pinfunction "121_121") (pintype "bidirectional"))
      (node (ref "X-SOUTH") (pin "127") (pinfunction "127_127") (pintype "bidirectional"))
      (node (ref "X-SOUTH") (pin "133") (pinfunction "133_133") (pintype "bidirectional"))
    )
    (net (code "251") (name "S_VW_CV") (class "Default")
      (node (ref "C13") (pin "1") (pinfunction "1_1") (pintype "passive"))
      (node (ref "R16") (pin "1") (pinfunction "1_1") (pintype "passive"))
      (node (ref "X-SOUTH") (pin "6") (pinfunction "6_6") (pintype "bidirectional"))
    )
    (net (code "252") (name "S_VW_OV") (class "Default")
      (node (ref "USW") (pin "7") (pinfunction "OUTB_7") (pintype "output"))
      (node (ref "X-SOUTH") (pin "5") (pinfunction "5_5") (pintype "bidirectional"))
    )
    (net (code "253") (name "S_VW_UV") (class "Default")
      (node (ref "USW") (pin "1") (pinfunction "OUTA_1") (pintype "output"))
      (node (ref "X-SOUTH") (pin "11") (pinfunction "11_11") (pintype "bidirectional"))
    )
    (net (code "254") (name "TDIG1") (class "Default")
      (node (ref "SENSOR") (pin "G27") (pinfunction "TDIG1_G27") (pintype "output"))
      (node (ref "U5") (pin "9") (pinfunction "B4_9") (pintype "bidirectional"))
    )
    (net (code "255") (name "TDIG2") (class "Default")
      (node (ref "SENSOR") (pin "G26") (pinfunction "TDIG2_G26") (pintype "output"))
      (node (ref "U6") (pin "11") (pinfunction "B2_11") (pintype "bidirectional"))
    )
    (net (code "256") (name "T_EXP1") (class "Default")
      (node (ref "SENSOR") (pin "H30") (pinfunction "T_EXP1_H30") (pintype "input"))
      (node (ref "U5") (pin "12") (pinfunction "B1_12") (pintype "bidirectional"))
    )
    (net (code "257") (name "T_EXP2") (class "Default")
      (node (ref "SENSOR") (pin "E29") (pinfunction "T_EXP2_E29") (pintype "input"))
      (node (ref "U6") (pin "10") (pinfunction "B3_10") (pintype "bidirectional"))
    )
    (net (code "258") (name "VRAMP1") (class "Default")
      (node (ref "C16") (pin "1") (pinfunction "1_1") (pintype "passive"))
      (node (ref "R23") (pin "1") (pinfunction "1_1") (pintype "passive"))
      (node (ref "SENSOR") (pin "G29") (pinfunction "VRAMP1_G29") (pintype "bidirectional"))
    )
    (net (code "259") (name "VRAMP2") (class "Default")
      (node (ref "C17") (pin "1") (pinfunction "1_1") (pintype "passive"))
      (node (ref "R23") (pin "2") (pinfunction "2_2") (pintype "passive"))
      (node (ref "SENSOR") (pin "F29") (pinfunction "VRAMP2_F29") (pintype "bidirectional"))
    )
    (net (code "260") (name "VTREF") (class "Default")
      (node (ref "C65") (pin "1") (pinfunction "1_1") (pintype "passive"))
      (node (ref "C91") (pin "2") (pinfunction "2_2") (pintype "passive"))
      (node (ref "R21") (pin "2") (pinfunction "2_2") (pintype "passive"))
      (node (ref "R24") (pin "1") (pinfunction "1_1") (pintype "passive"))
      (node (ref "SENSOR") (pin "B2") (pinfunction "VTREF_B2") (pintype "bidirectional"))
      (node (ref "U3") (pin "4") (pinfunction "OUT_4") (pintype "power_in"))
    )
    (net (code "261") (name "VTSIG") (class "Default")
      (node (ref "C66") (pin "1") (pinfunction "1_1") (pintype "passive"))
      (node (ref "R24") (pin "2") (pinfunction "2_2") (pintype "passive"))
      (node (ref "SENSOR") (pin "C2") (pinfunction "VTSIG_C2") (pintype "bidirectional"))
    )
    (net (code "262") (name "unconnected-(U1-NC-Pad2)") (class "Default")
      (node (ref "U1") (pin "2") (pinfunction "NC_2") (pintype "no_connect"))
    )
    (net (code "263") (name "unconnected-(U1-NC-Pad4)") (class "Default")
      (node (ref "U1") (pin "4") (pinfunction "NC_4") (pintype "no_connect"))
    )
    (net (code "264") (name "unconnected-(U1-NC-Pad5)") (class "Default")
      (node (ref "U1") (pin "5") (pinfunction "NC_5") (pintype "no_connect"))
    )
    (net (code "265") (name "unconnected-(U2-NC-Pad2)") (class "Default")
      (node (ref "U2") (pin "2") (pinfunction "NC_2") (pintype "no_connect"))
    )
    (net (code "266") (name "unconnected-(U2-NC-Pad4)") (class "Default")
      (node (ref "U2") (pin "4") (pinfunction "NC_4") (pintype "no_connect"))
    )
    (net (code "267") (name "unconnected-(U2-NC-Pad5)") (class "Default")
      (node (ref "U2") (pin "5") (pinfunction "NC_5") (pintype "no_connect"))
    )
    (net (code "268") (name "unconnected-(U7-OS-Pad3)") (class "Default")
      (node (ref "U7") (pin "3") (pinfunction "OS_3") (pintype "output"))
    )
    (net (code "269") (name "unconnected-(X-NORTH-PadM1)") (class "Default")
      (node (ref "X-NORTH") (pin "M1") (pinfunction "M1_M1") (pintype "bidirectional"))
    )
    (net (code "270") (name "unconnected-(X-NORTH-PadM2)") (class "Default")
      (node (ref "X-NORTH") (pin "M2") (pinfunction "M2_M2") (pintype "bidirectional"))
    )
    (net (code "271") (name "unconnected-(X-SOUTH-PadM1)") (class "Default")
      (node (ref "X-SOUTH") (pin "M1") (pinfunction "M1_M1") (pintype "bidirectional"))
    )
    (net (code "272") (name "unconnected-(X-SOUTH-PadM2)") (class "Default")
      (node (ref "X-SOUTH") (pin "M2") (pinfunction "M2_M2") (pintype "bidirectional"))
    )
  )
)
